# ProDoc_Board_ESP_AI_2024-12-05.net
KiCad netlist of a schematic drawn in EasyEDA Pro
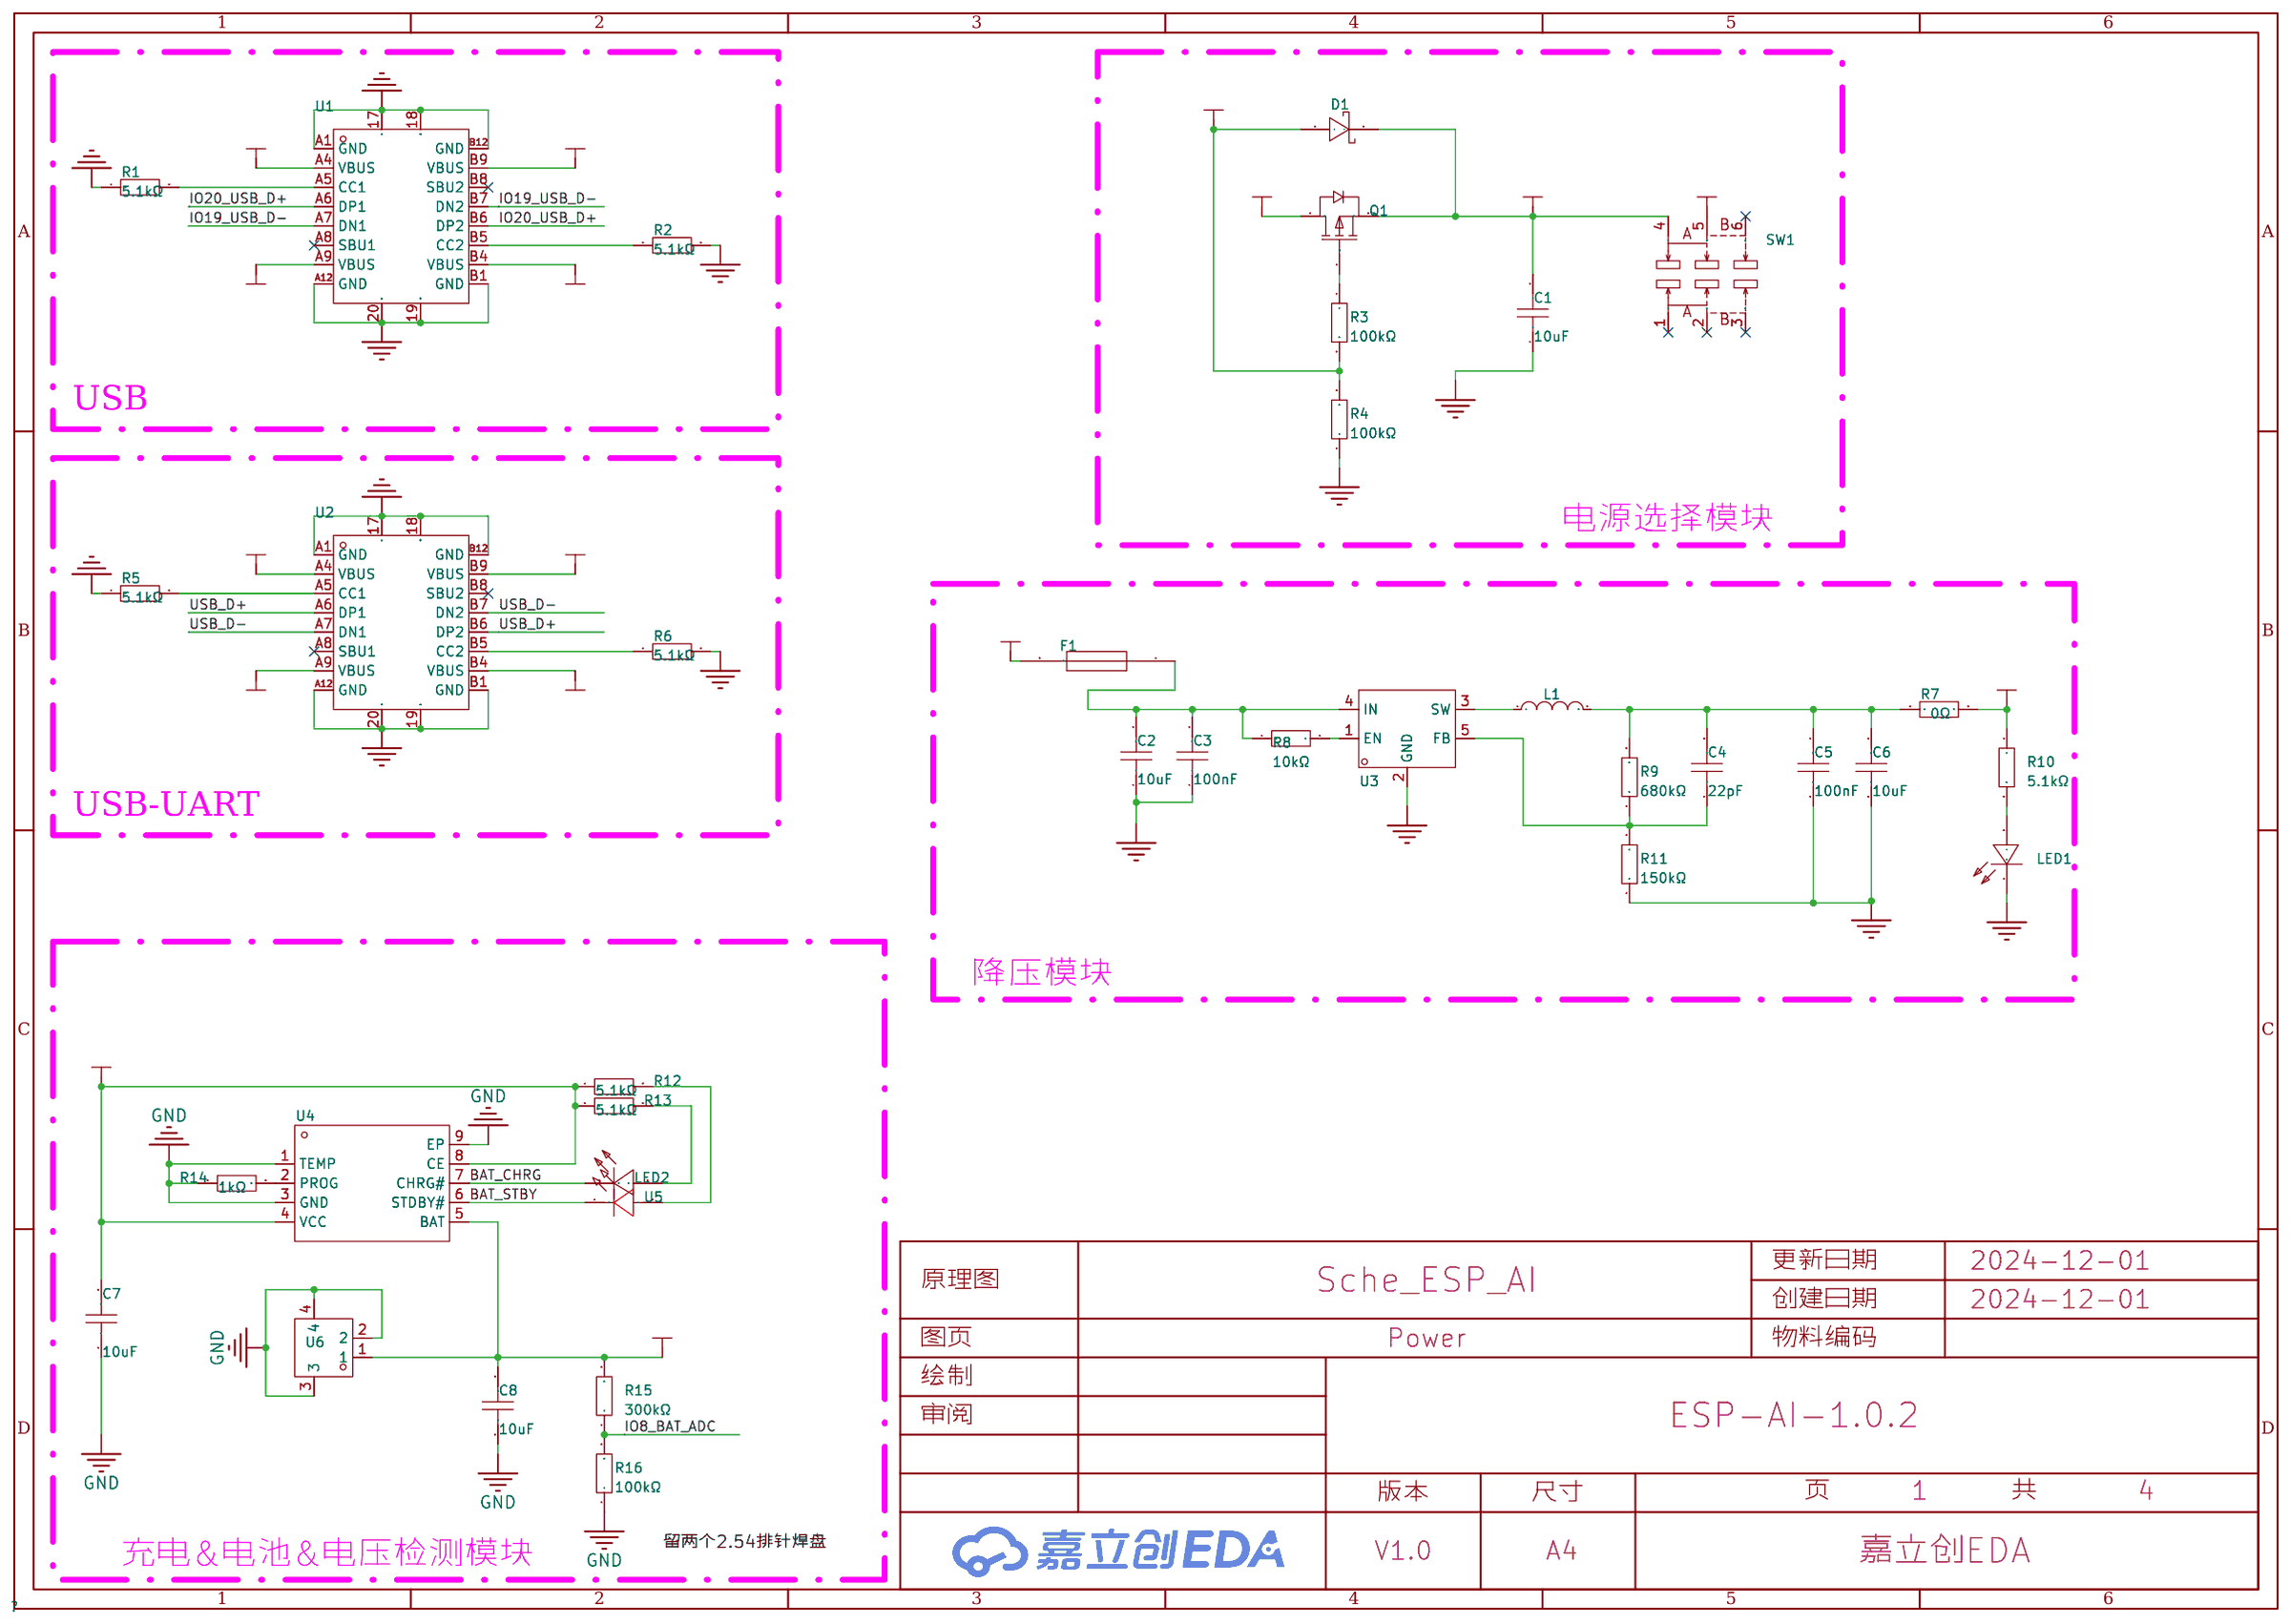
[diagram p0: Power]
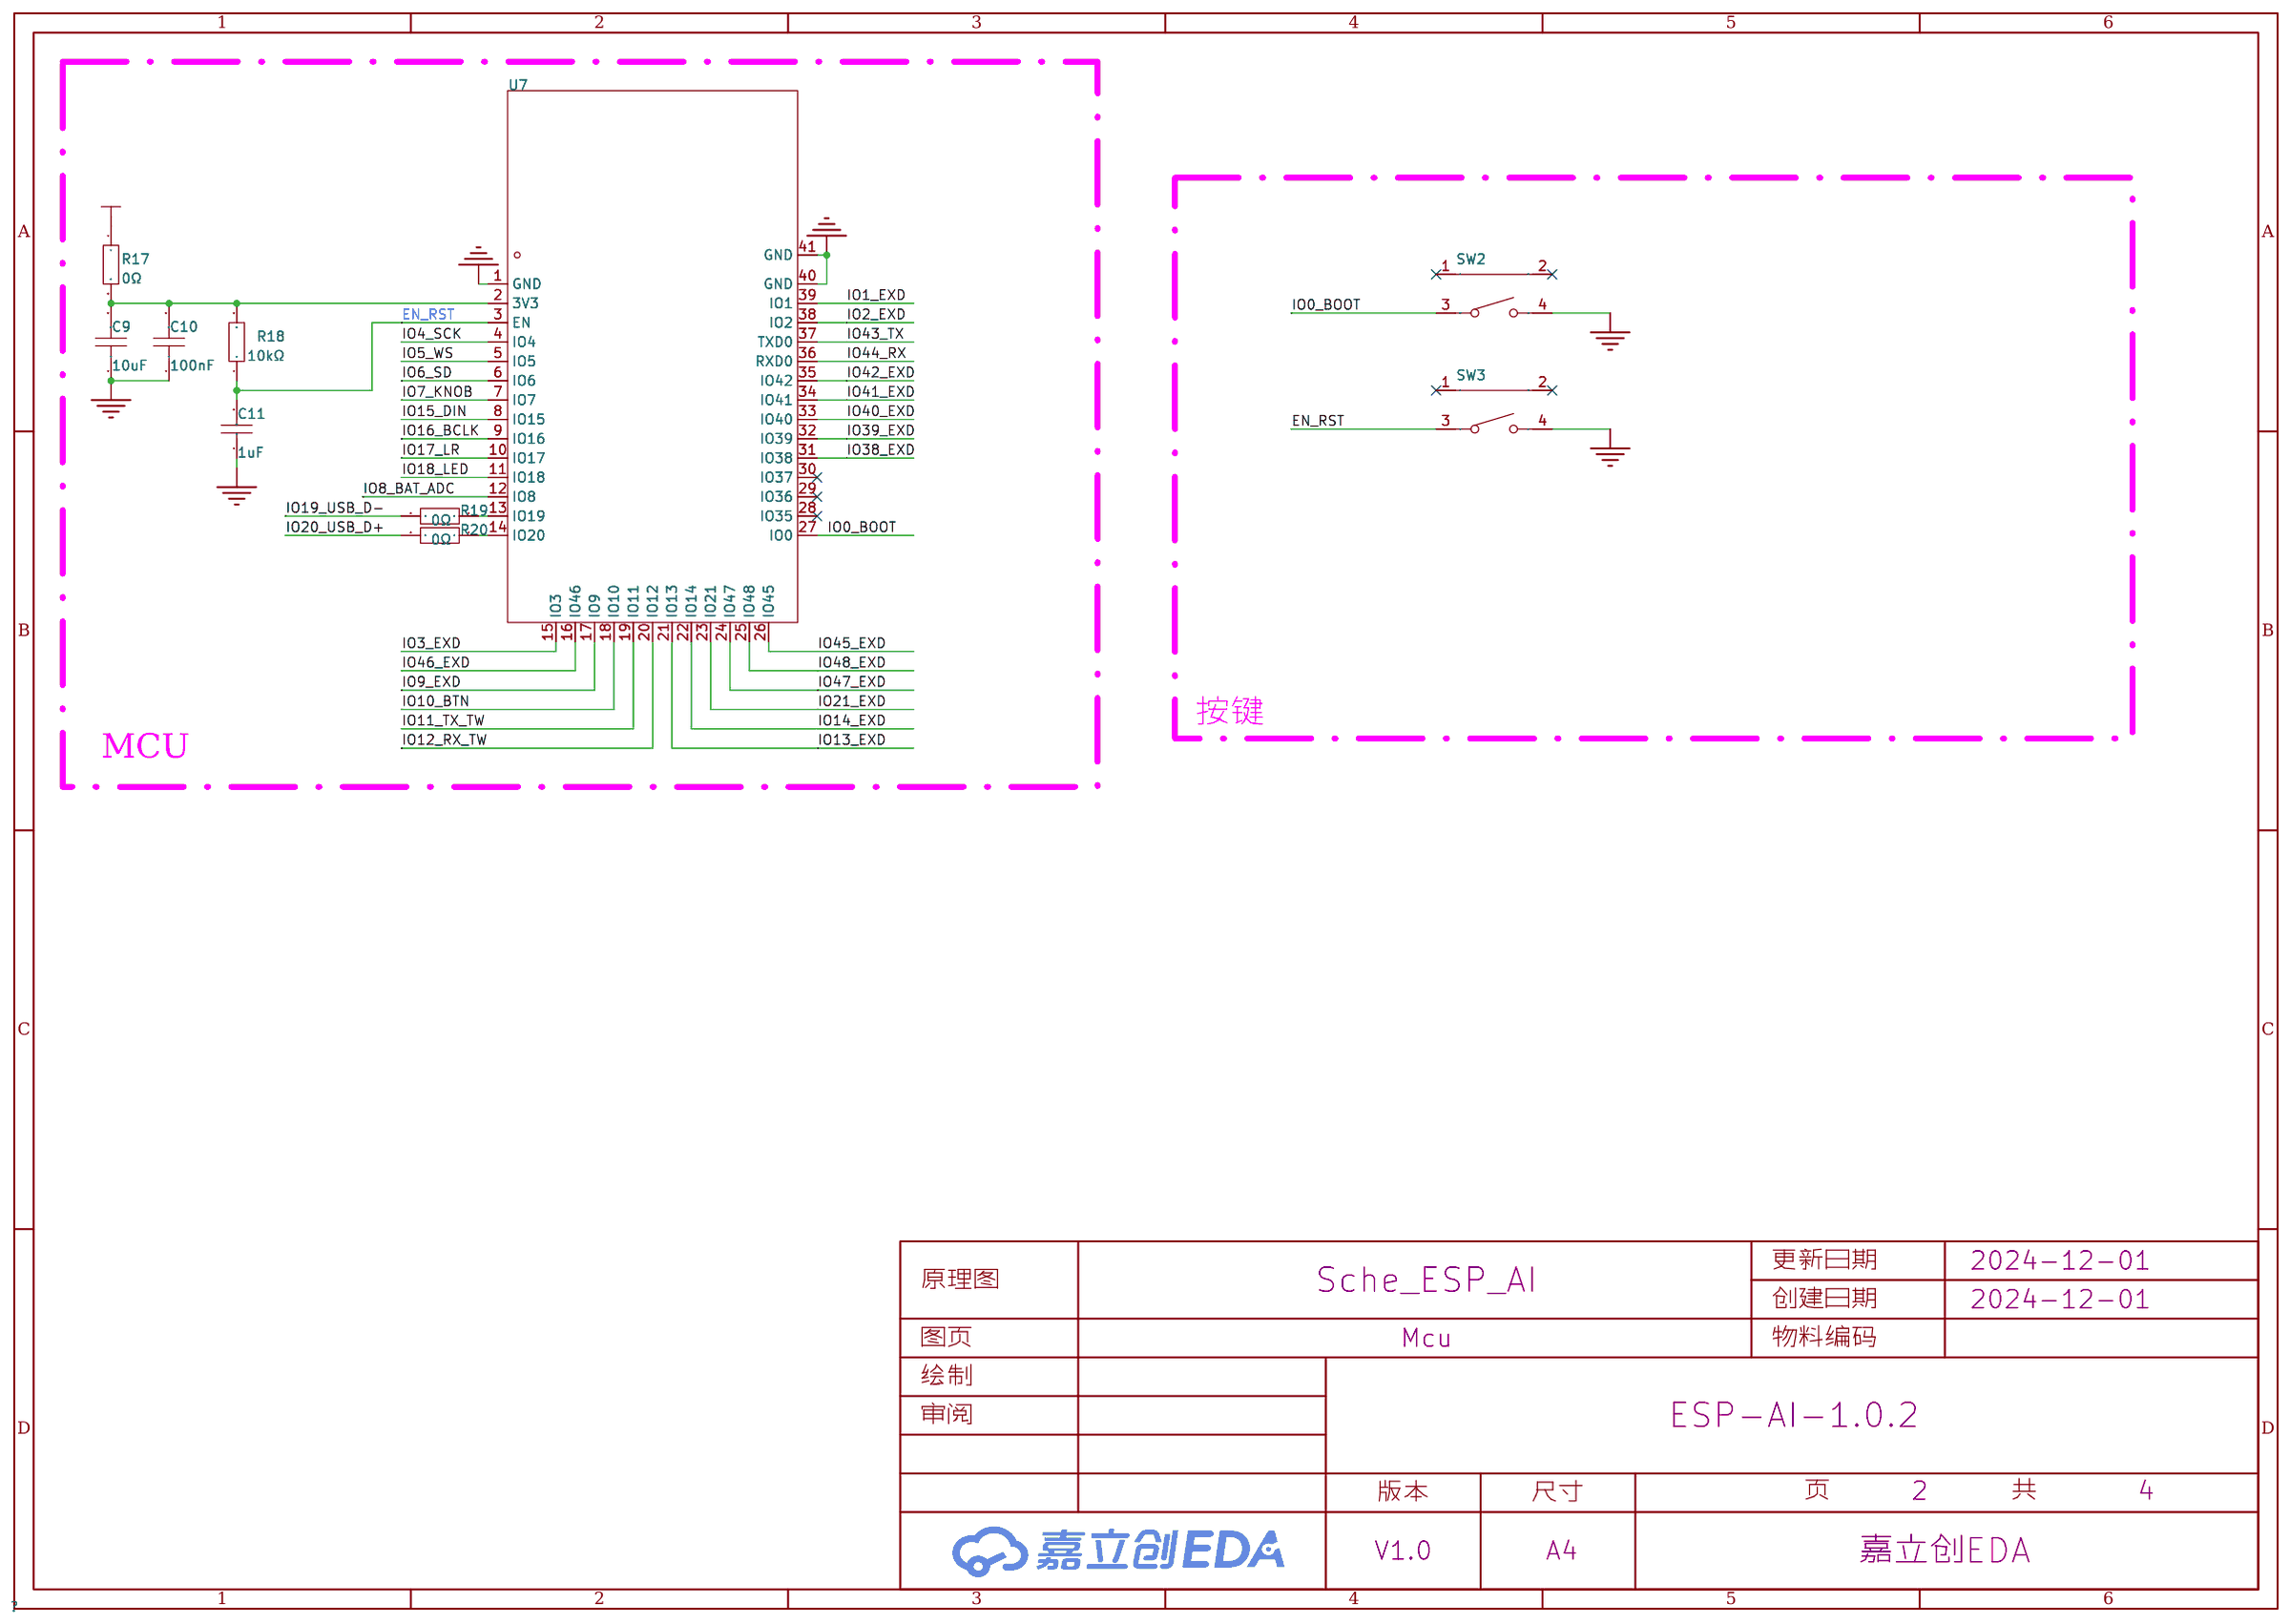
[diagram p1: Mcu]
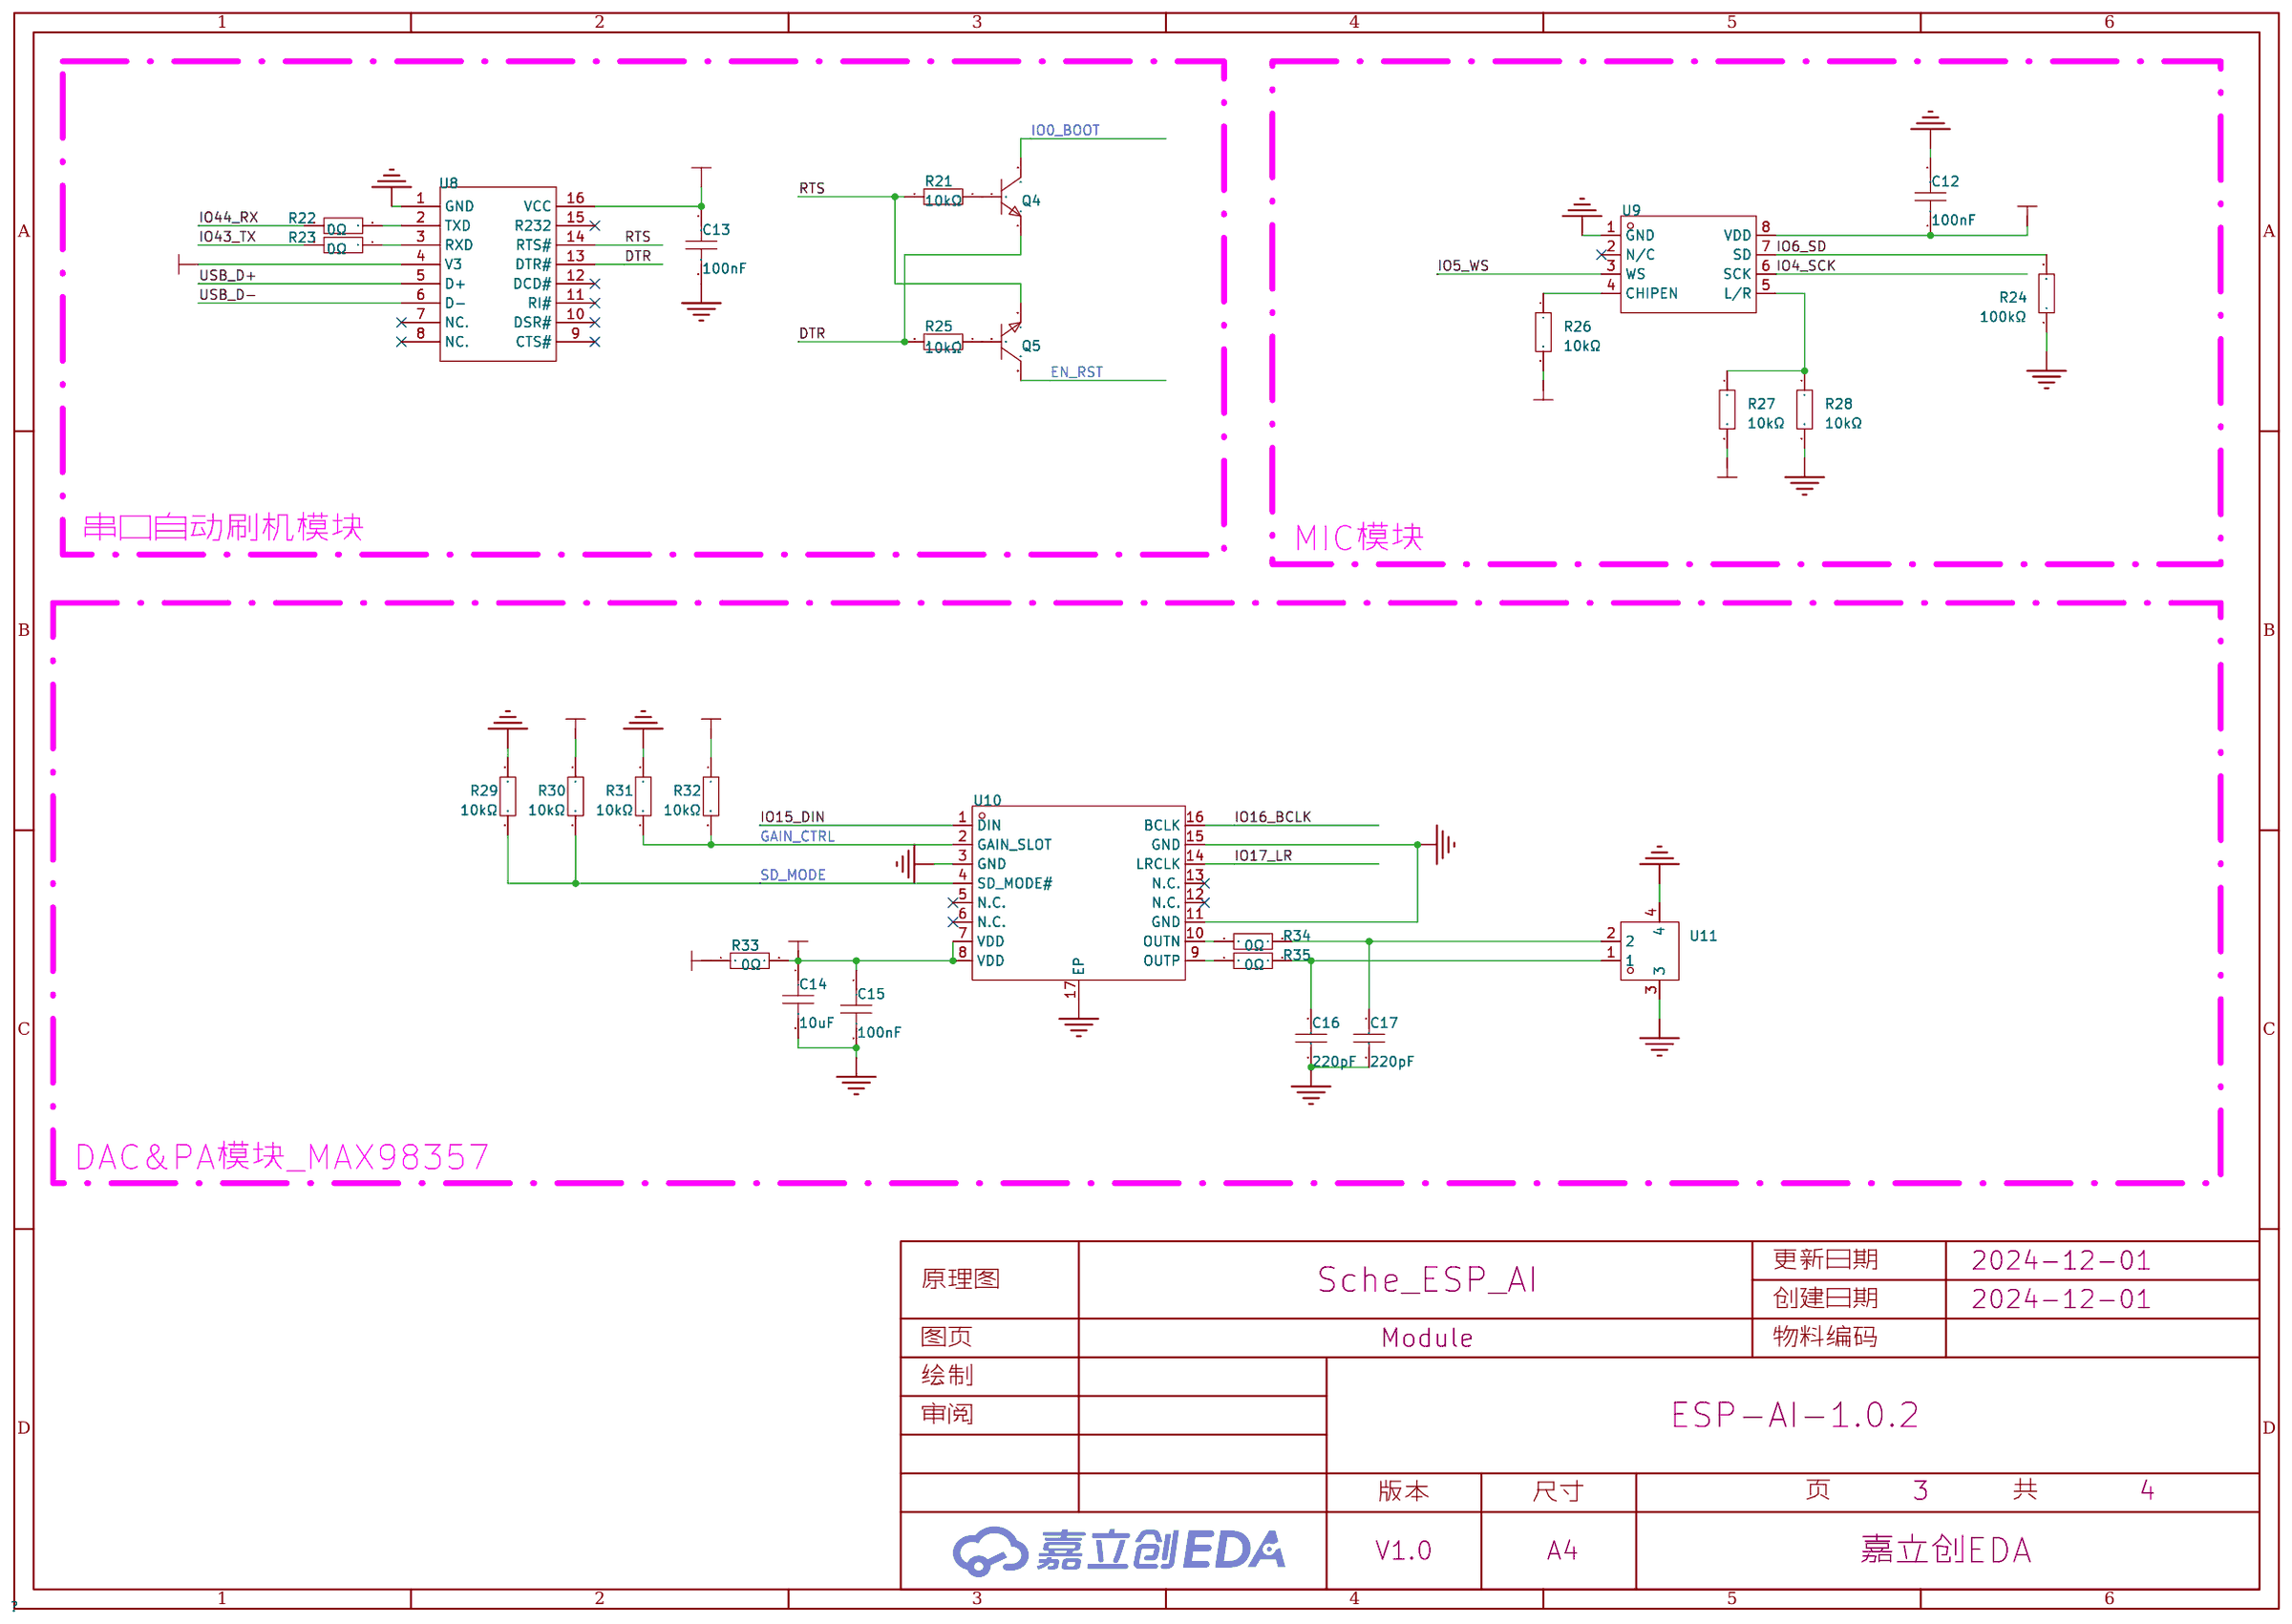
[diagram p2: Module]
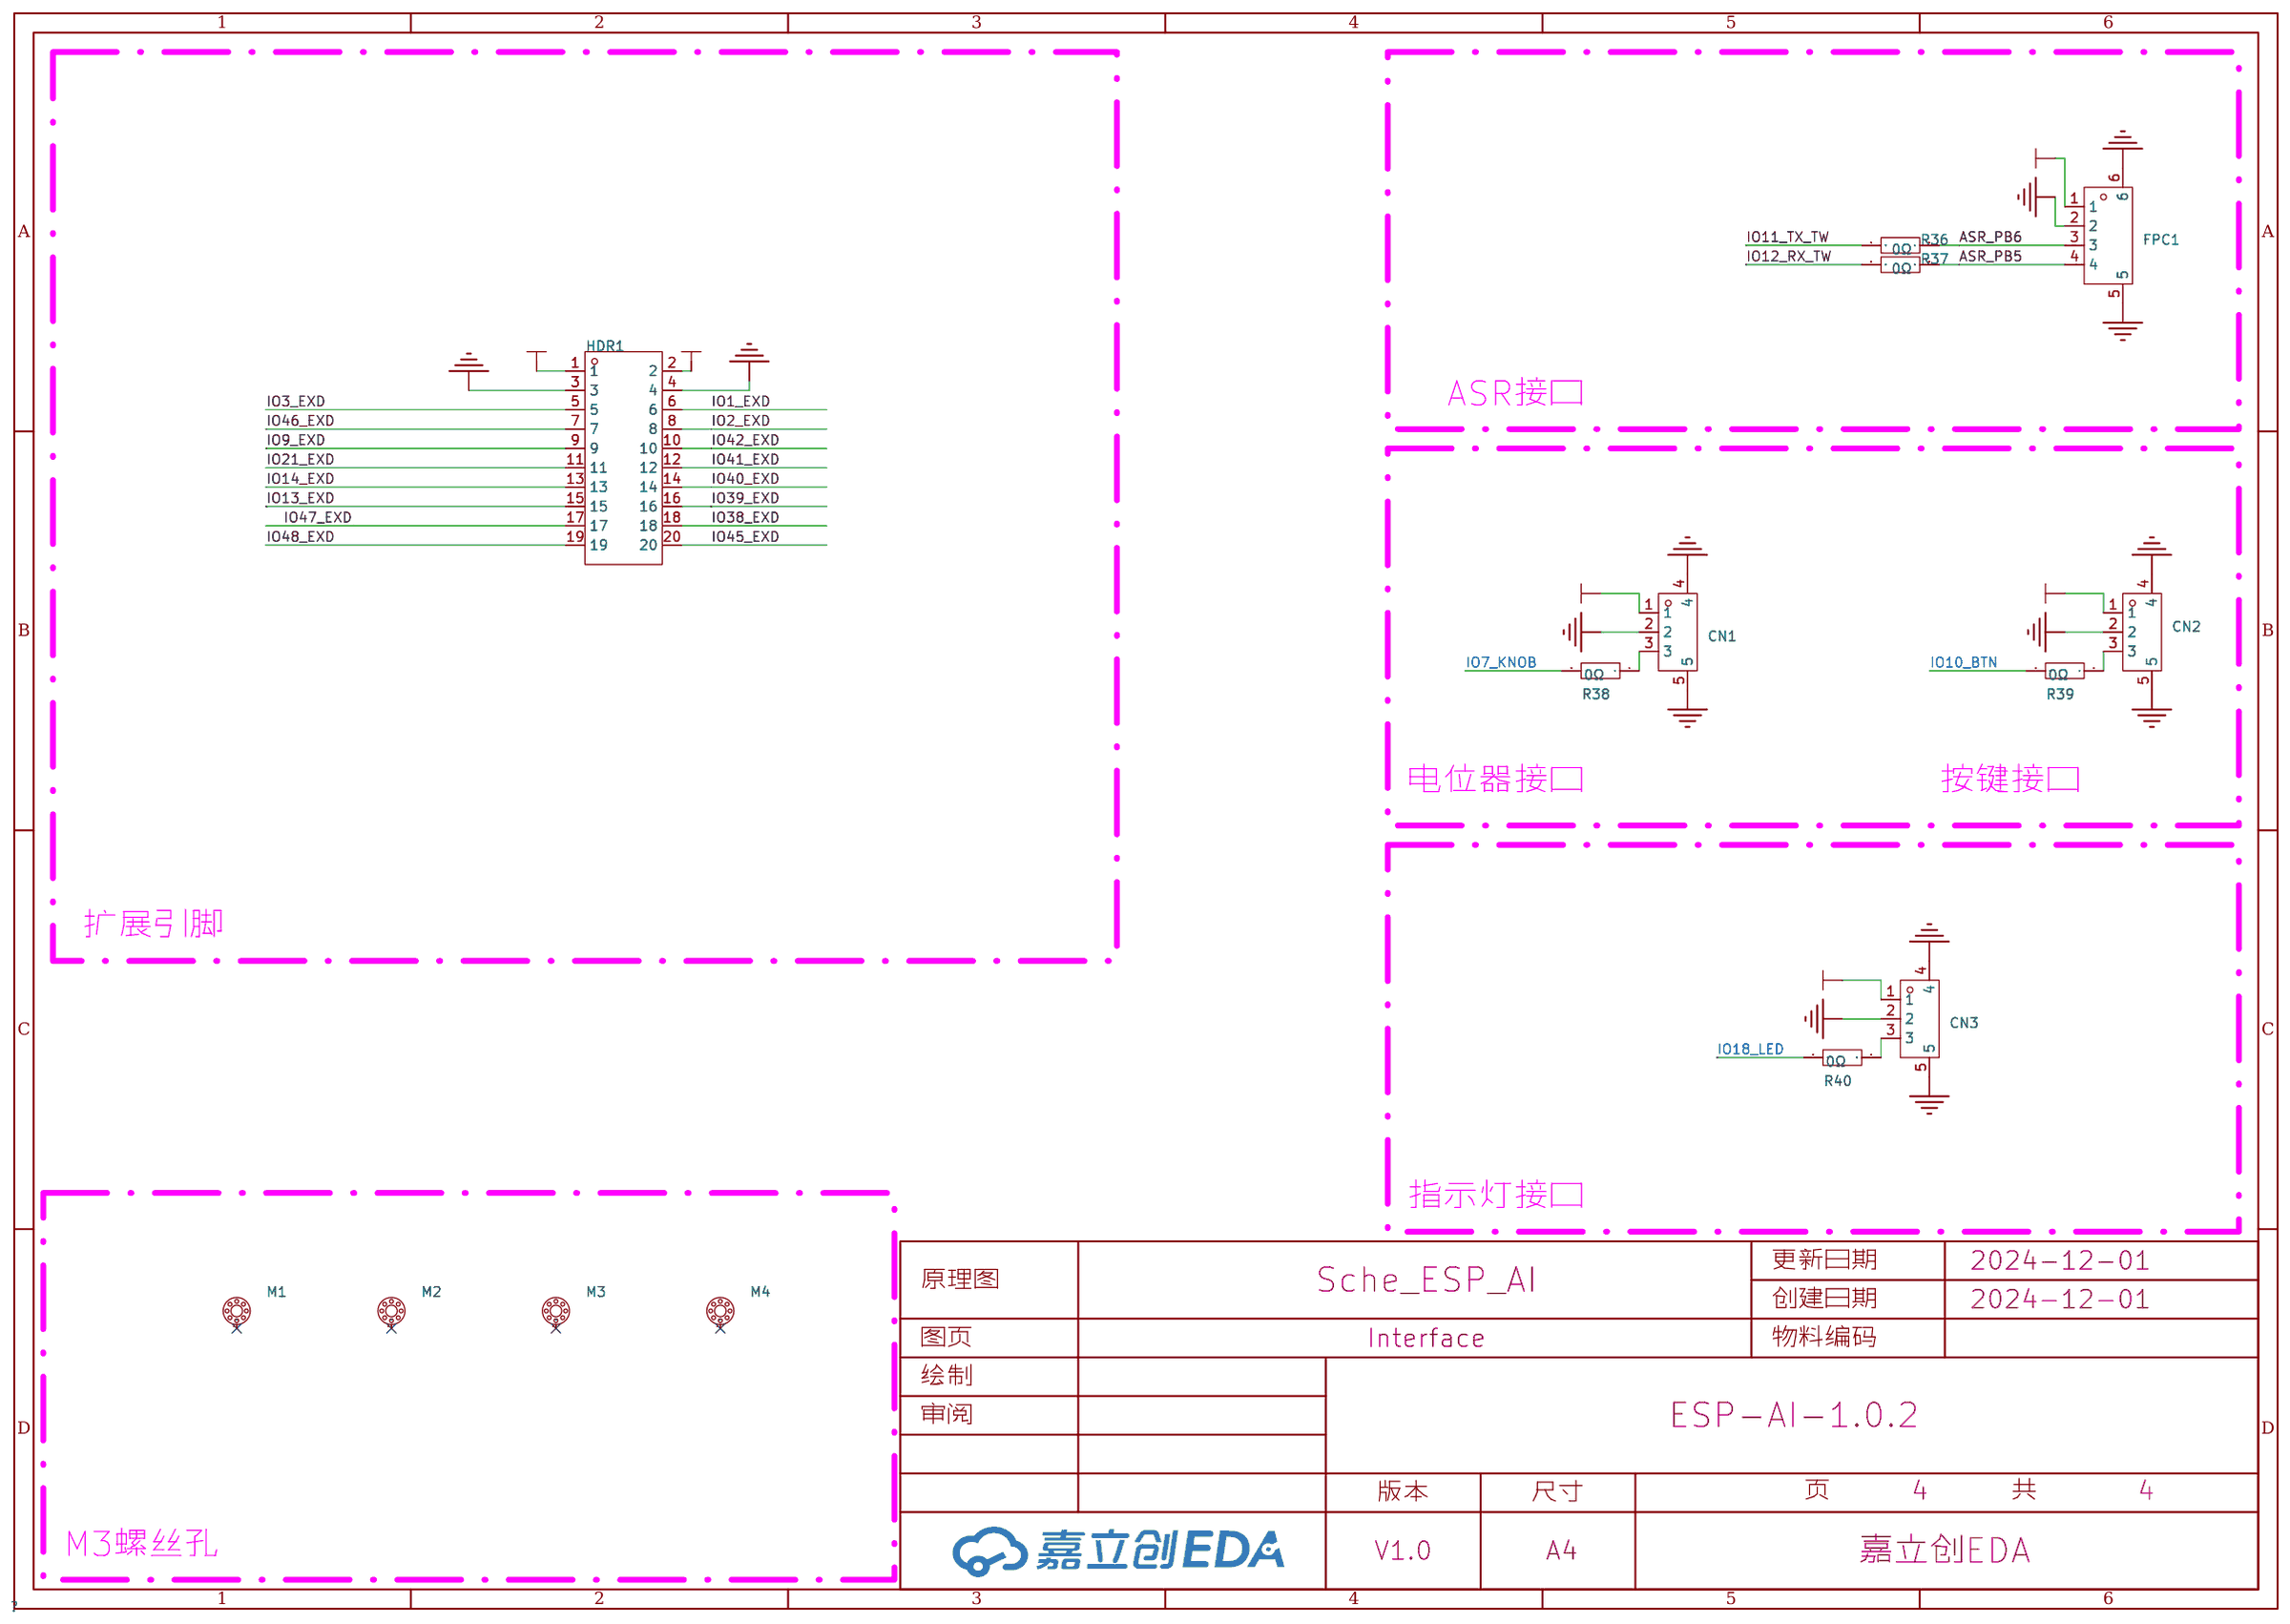
[diagram p3: Interface]

(export (version "E")
  (design (tool "Eeschema 10.0.6"))
  (components
    (comp (ref "C1")
      (value "10uF")
      (footprint "easyedapro:C0603")
      (description "容值:10uF;精度:±10%;额定电压:10V;材质(温度系数):X5R;")
      (fields
        (field (name "Manufacturer Part") "CL10A106KP8NNNC")
        (field (name "Manufacturer") "SAMSUNG(三星)")
      )
      (libsource (lib "easyedapro") (part "CL10A106KP8NNNC"))
    )
    (comp (ref "C2")
      (value "10uF")
      (footprint "easyedapro:C0603")
      (description "容值:10uF;精度:±10%;额定电压:10V;材质(温度系数):X5R;")
      (fields
        (field (name "Manufacturer Part") "CL10A106KP8NNNC")
        (field (name "Manufacturer") "SAMSUNG(三星)")
      )
      (libsource (lib "easyedapro") (part "CL10A106KP8NNNC"))
    )
    (comp (ref "C3")
      (value "100nF")
      (footprint "easyedapro:C0603")
      (description "容值:100nF;精度:±10%;额定电压:50V;材质(温度系数):X7R;")
      (fields
        (field (name "Manufacturer Part") "CC0603KRX7R9BB104")
        (field (name "Manufacturer") "YAGEO(国巨)")
      )
      (libsource (lib "easyedapro") (part "CC0603KRX7R9BB104"))
    )
    (comp (ref "C4")
      (value "22pF")
      (footprint "easyedapro:C0603")
      (description "容值:100nF;精度:±10%;额定电压:50V;材质(温度系数):X7R;")
      (fields
        (field (name "Manufacturer Part") "CL10C220JB8NNNC")
        (field (name "Manufacturer") "SAMSUNG(三星)")
      )
      (libsource (lib "easyedapro") (part "CC0603KRX7R9BB104"))
    )
    (comp (ref "C5")
      (value "100nF")
      (footprint "easyedapro:C0603")
      (description "容值:100nF;精度:±10%;额定电压:50V;材质(温度系数):X7R;")
      (fields
        (field (name "Manufacturer Part") "CC0603KRX7R9BB104")
        (field (name "Manufacturer") "YAGEO(国巨)")
      )
      (libsource (lib "easyedapro") (part "CC0603KRX7R9BB104"))
    )
    (comp (ref "C6")
      (value "10uF")
      (footprint "easyedapro:C0603")
      (description "容值:10uF;精度:±10%;额定电压:10V;材质(温度系数):X5R;")
      (fields
        (field (name "Manufacturer Part") "CL10A106KP8NNNC")
        (field (name "Manufacturer") "SAMSUNG(三星)")
      )
      (libsource (lib "easyedapro") (part "CL10A106KP8NNNC"))
    )
    (comp (ref "C7")
      (value "10uF")
      (footprint "easyedapro:C0603")
      (description "容值:10uF;精度:±10%;额定电压:10V;材质(温度系数):X5R;")
      (fields
        (field (name "Manufacturer Part") "CL10A106KP8NNNC")
        (field (name "Manufacturer") "SAMSUNG(三星)")
      )
      (libsource (lib "easyedapro") (part "CL10A106KP8NNNC"))
    )
    (comp (ref "C8")
      (value "10uF")
      (footprint "easyedapro:C0603")
      (description "容值:10uF;精度:±10%;额定电压:10V;材质(温度系数):X5R;")
      (fields
        (field (name "Manufacturer Part") "CL10A106KP8NNNC")
        (field (name "Manufacturer") "SAMSUNG(三星)")
      )
      (libsource (lib "easyedapro") (part "CL10A106KP8NNNC"))
    )
    (comp (ref "D1")
      (value "B5819W SL")
      (footprint "easyedapro:SOD-123_L2.7-W1.6-LS3.7-RD-1")
      (description "正向压降(Vf):600mV@1A;直流反向耐压(Vr):40V;整流电流:1A;")
      (fields (field (name "Manufacturer") "CJ(江苏长电/长晶)"))
      (libsource (lib "easyedapro") (part "B5819W_C8598"))
    )
    (comp (ref "F1")
      (value "JK-SMD0603-100L")
      (footprint "easyedapro:F0603")
      (description "最大电压:6V;最大电流:50A;保持电流:1A;跳闸电流:2A;")
      (fields (field (name "Manufacturer") "JK(金科)"))
      (libsource (lib "easyedapro") (part "JK-SMD0603-100L"))
    )
    (comp (ref "L1")
      (value "2.2uH")
      (footprint "easyedapro:IND-SMD_L4.0-W4.0")
      (description "电感值:2.2uH;精度:±20%;额定电流:2.2A;饱和电流(Isat):3A;类型:-;")
      (fields (field (name "Manufacturer Part") "SPH4018H2R2MT") (field (name "Manufacturer") "Sunlord(顺络)"))
      (libsource (lib "easyedapro") (part "SPH4018H2R2MT"))
    )
    (comp (ref "LED1")
      (value "KT-0603R")
      (footprint "easyedapro:LED0603-RD")
      (description "发光颜色:红色;功率:-;正向电流:-;主波长:-;二极管配置:-;透镜颜色:-;色温:-;发光角度:-;载带方式:-;工作温度:-40°C~+85°C;")
      (fields (field (name "Manufacturer") "KENTO"))
      (libsource (lib "easyedapro") (part "KT-0603R"))
    )
    (comp (ref "LED2")
      (value "KT-0603R")
      (footprint "easyedapro:LED0603-RD")
      (description "发光颜色:红色;功率:-;正向电流:-;主波长:-;二极管配置:-;透镜颜色:-;色温:-;发光角度:-;载带方式:-;工作温度:-40°C~+85°C;")
      (fields (field (name "Manufacturer") "KENTO"))
      (libsource (lib "easyedapro") (part "KT-0603R"))
    )
    (comp (ref "Q1")
      (value "AO3401A")
      (footprint "easyedapro:SOT-23_L2.9-W1.3-P1.90-LS2.4-BR")
      (fields (field (name "Manufacturer") "AOS"))
      (libsource (lib "easyedapro") (part "AO3401A"))
    )
    (comp (ref "R1")
      (value "5.1kΩ")
      (footprint "easyedapro:R0603")
      (description "电阻类型:厚膜电阻;阻值:5.1kΩ;精度:±1%;功率:100mW;最大工作电压:75V;温度系数:±100ppm/°C;")
      (fields
        (field (name "Manufacturer Part") "0603WAF5101T5E")
        (field (name "Manufacturer") "UNI-ROYAL(厚声)")
      )
      (libsource (lib "easyedapro") (part "0603WAF5101T5E"))
    )
    (comp (ref "R2")
      (value "5.1kΩ")
      (footprint "easyedapro:R0603")
      (description "电阻类型:厚膜电阻;阻值:5.1kΩ;精度:±1%;功率:100mW;最大工作电压:75V;温度系数:±100ppm/°C;")
      (fields
        (field (name "Manufacturer Part") "0603WAF5101T5E")
        (field (name "Manufacturer") "UNI-ROYAL(厚声)")
      )
      (libsource (lib "easyedapro") (part "0603WAF5101T5E"))
    )
    (comp (ref "R3")
      (value "100kΩ")
      (footprint "easyedapro:R0603")
      (description "电阻类型:厚膜电阻;阻值:100kΩ;精度:±1%;功率:100mW;最大工作电压:75V;温度系数:±100ppm/°C;")
      (fields
        (field (name "Manufacturer Part") "0603WAF1003T5E")
        (field (name "Manufacturer") "UNI-ROYAL(厚声)")
      )
      (libsource (lib "easyedapro") (part "0603WAF1003T5E"))
    )
    (comp (ref "R4")
      (value "100kΩ")
      (footprint "easyedapro:R0603")
      (description "电阻类型:厚膜电阻;阻值:100kΩ;精度:±1%;功率:100mW;最大工作电压:75V;温度系数:±100ppm/°C;")
      (fields
        (field (name "Manufacturer Part") "0603WAF1003T5E")
        (field (name "Manufacturer") "UNI-ROYAL(厚声)")
      )
      (libsource (lib "easyedapro") (part "0603WAF1003T5E"))
    )
    (comp (ref "R5")
      (value "5.1kΩ")
      (footprint "easyedapro:R0603")
      (description "电阻类型:厚膜电阻;阻值:5.1kΩ;精度:±1%;功率:100mW;最大工作电压:75V;温度系数:±100ppm/°C;")
      (fields
        (field (name "Manufacturer Part") "0603WAF5101T5E")
        (field (name "Manufacturer") "UNI-ROYAL(厚声)")
      )
      (libsource (lib "easyedapro") (part "0603WAF5101T5E"))
    )
    (comp (ref "R6")
      (value "5.1kΩ")
      (footprint "easyedapro:R0603")
      (description "电阻类型:厚膜电阻;阻值:5.1kΩ;精度:±1%;功率:100mW;最大工作电压:75V;温度系数:±100ppm/°C;")
      (fields
        (field (name "Manufacturer Part") "0603WAF5101T5E")
        (field (name "Manufacturer") "UNI-ROYAL(厚声)")
      )
      (libsource (lib "easyedapro") (part "0603WAF5101T5E"))
    )
    (comp (ref "R7")
      (value "0Ω")
      (footprint "easyedapro:R0603_1")
      (description "电阻类型:厚膜电阻;阻值:0Ω;精度:±1%;功率:100mW;最大工作电压:75V;")
      (fields
        (field (name "Manufacturer Part") "0603WAF0000T5E")
        (field (name "Manufacturer") "UNI-ROYAL(厚声)")
      )
      (libsource (lib "easyedapro") (part "0603WAF0000T5E"))
    )
    (comp (ref "R8")
      (value "10kΩ")
      (footprint "easyedapro:R0603_1")
      (description "电阻类型:厚膜电阻;阻值:10kΩ;精度:±1%;功率:100mW;最大工作电压:75V;温度系数:±100ppm/℃;")
      (fields
        (field (name "Manufacturer Part") "0603WAF1002T5E")
        (field (name "Manufacturer") "UNI-ROYAL(厚声)")
      )
      (libsource (lib "easyedapro") (part "0603WAF1002T5E"))
    )
    (comp (ref "R9")
      (value "680kΩ")
      (footprint "easyedapro:R0603_1")
      (description "电阻类型:厚膜电阻;阻值:680kΩ;精度:±1%;功率:100mW;最大工作电压:75V;温度系数:±100ppm/℃;")
      (fields
        (field (name "Manufacturer Part") "0603WAF6803T5E")
        (field (name "Manufacturer") "UNI-ROYAL(厚声)")
      )
      (libsource (lib "easyedapro") (part "0603WAF6803T5E"))
    )
    (comp (ref "R10")
      (value "5.1kΩ")
      (footprint "easyedapro:R0603")
      (description "电阻类型:厚膜电阻;阻值:5.1kΩ;精度:±1%;功率:100mW;最大工作电压:75V;温度系数:±100ppm/°C;")
      (fields
        (field (name "Manufacturer Part") "0603WAF5101T5E")
        (field (name "Manufacturer") "UNI-ROYAL(厚声)")
      )
      (libsource (lib "easyedapro") (part "0603WAF5101T5E"))
    )
    (comp (ref "R11")
      (value "150kΩ")
      (footprint "easyedapro:R0603_1")
      (description "电阻类型:厚膜电阻;阻值:150kΩ;精度:±1%;功率:100mW;最大工作电压:75V;温度系数:±100ppm/℃;")
      (fields
        (field (name "Manufacturer Part") "0603WAF1503T5E")
        (field (name "Manufacturer") "UNI-ROYAL(厚声)")
      )
      (libsource (lib "easyedapro") (part "0603WAF1503T5E"))
    )
    (comp (ref "R12")
      (value "5.1kΩ")
      (footprint "easyedapro:R0603")
      (description "电阻类型:厚膜电阻;阻值:5.1kΩ;精度:±1%;功率:100mW;最大工作电压:75V;温度系数:±100ppm/°C;")
      (fields
        (field (name "Manufacturer Part") "0603WAF5101T5E")
        (field (name "Manufacturer") "UNI-ROYAL(厚声)")
      )
      (libsource (lib "easyedapro") (part "0603WAF5101T5E"))
    )
    (comp (ref "R13")
      (value "5.1kΩ")
      (footprint "easyedapro:R0603")
      (description "电阻类型:厚膜电阻;阻值:5.1kΩ;精度:±1%;功率:100mW;最大工作电压:75V;温度系数:±100ppm/°C;")
      (fields
        (field (name "Manufacturer Part") "0603WAF5101T5E")
        (field (name "Manufacturer") "UNI-ROYAL(厚声)")
      )
      (libsource (lib "easyedapro") (part "0603WAF5101T5E"))
    )
    (comp (ref "R14")
      (value "1kΩ")
      (footprint "easyedapro:R0603")
      (description "电阻类型:厚膜电阻;阻值:1kΩ;精度:±1%;功率:100mW;最大工作电压:75V;温度系数:±100ppm/°C;")
      (fields
        (field (name "Manufacturer Part") "0603WAF1001T5E")
        (field (name "Manufacturer") "UNI-ROYAL(厚声)")
      )
      (libsource (lib "easyedapro") (part "0603WAF1001T5E"))
    )
    (comp (ref "R15")
      (value "300kΩ")
      (footprint "easyedapro:R0603")
      (description "电阻类型:厚膜电阻;阻值:300kΩ;精度:±1%;功率:100mW;最大工作电压:75V;温度系数:±100ppm/°C;")
      (fields
        (field (name "Manufacturer Part") "0603WAF3003T5E")
        (field (name "Manufacturer") "UNI-ROYAL(厚声)")
      )
      (libsource (lib "easyedapro") (part "0603WAF3003T5E"))
    )
    (comp (ref "R16")
      (value "100kΩ")
      (footprint "easyedapro:R0603")
      (description "电阻类型:厚膜电阻;阻值:100kΩ;精度:±1%;功率:100mW;最大工作电压:75V;温度系数:±100ppm/°C;")
      (fields
        (field (name "Manufacturer Part") "0603WAF1003T5E")
        (field (name "Manufacturer") "UNI-ROYAL(厚声)")
      )
      (libsource (lib "easyedapro") (part "0603WAF1003T5E"))
    )
    (comp (ref "SW1")
      (value "MST22D18G2 125")
      (footprint "easyedapro:SW-SMD_MST22D18G2")
      (description "电路结构:双刀双掷;安装方式:立贴;开关颜色:黑色;额定电流(DC):100mA;额定电压(DC):12V;机械寿命:1万次;")
      (fields (field (name "Manufacturer") "SHOU HAN(首韩)"))
      (libsource (lib "easyedapro") (part "MST22D18G2 125"))
    )
    (comp (ref "U1")
      (value "24018-UCAF001-A")
      (footprint "easyedapro:TYPE-C-USB-SMD_CF003")
      (description "TYPE C 16P母座加高1.0 H=4.25无弹")
      (fields (field (name "Manufacturer") "MINTRON(明硕)"))
      (libsource (lib "easyedapro") (part "24018-UCAF001-A"))
    )
    (comp (ref "U2")
      (value "24018-UCAF001-A")
      (footprint "easyedapro:TYPE-C-USB-SMD_CF003")
      (description "TYPE C 16P母座加高1.0 H=4.25无弹")
      (fields (field (name "Manufacturer") "MINTRON(明硕)"))
      (libsource (lib "easyedapro") (part "24018-UCAF001-A"))
    )
    (comp (ref "U3")
      (value "ETA3409S2F")
      (footprint "easyedapro:SOT-23-5_L2.9-W1.6-P0.95-LS2.8-BL_1")
      (fields (field (name "Manufacturer") "ETA(钰泰）"))
      (libsource (lib "easyedapro") (part "ETA3409S2F"))
    )
    (comp (ref "U4")
      (value "AP5056")
      (footprint "easyedapro:SOP-8_L4.9-W3.9-P1.27-LS6.0-BL-EP")
      (description "常用锂电池充电芯片，功能同TP4056")
      (fields (field (name "Manufacturer") "chipown(芯朋微电子)"))
      (libsource (lib "easyedapro") (part "AP5056"))
    )
    (comp (ref "U5")
      (value "19-217/GHC-YR1S2/6T")
      (footprint "easyedapro:LED0603-RD_GREEN")
      (fields (field (name "Manufacturer") "EVERLIGHT(亿光)"))
      (libsource (lib "easyedapro") (part "19-217/ghc-yr1s2/6t"))
    )
    (comp (ref "U6")
      (value "HCZZ0015-2")
      (footprint "easyedapro:CONN-SMD_HCZZ0015-2")
      (fields (field (name "Manufacturer") "HC(虹成电子)"))
      (libsource (lib "easyedapro") (part "HCZZ0015-2"))
    )
    (comp (ref "C9")
      (value "10uF")
      (footprint "easyedapro:C0603")
      (description "容值:10uF;精度:±10%;额定电压:10V;材质(温度系数):X5R;")
      (fields
        (field (name "Manufacturer Part") "CL10A106KP8NNNC")
        (field (name "Manufacturer") "SAMSUNG(三星)")
      )
      (libsource (lib "easyedapro") (part "CL10A106KP8NNNC"))
    )
    (comp (ref "C10")
      (value "100nF")
      (footprint "easyedapro:C0603")
      (description "容值:100nF;精度:±10%;额定电压:50V;材质(温度系数):X7R;")
      (fields
        (field (name "Manufacturer Part") "CC0603KRX7R9BB104")
        (field (name "Manufacturer") "YAGEO(国巨)")
      )
      (libsource (lib "easyedapro") (part "CC0603KRX7R9BB104"))
    )
    (comp (ref "C11")
      (value "1uF")
      (footprint "easyedapro:C0603_1")
      (description "容值:1uF;精度:±10%;额定电压:50V;材质(温度系数):X5R;")
      (fields
        (field (name "Manufacturer Part") "CL10A105KB8NNNC")
        (field (name "Manufacturer") "SAMSUNG(三星)")
      )
      (libsource (lib "easyedapro") (part "CL10A105KB8NNNC"))
    )
    (comp (ref "R17")
      (value "0Ω")
      (footprint "easyedapro:R0603_1")
      (description "电阻类型:厚膜电阻;阻值:0Ω;精度:±1%;功率:100mW;")
      (fields
        (field (name "Manufacturer Part") "0603WAF0000T5E")
        (field (name "Manufacturer") "UNI-ROYAL(厚声)")
      )
      (libsource (lib "easyedapro") (part "0603WAF0000T5E"))
    )
    (comp (ref "R18")
      (value "10kΩ")
      (footprint "easyedapro:R0603_1")
      (description "电阻类型:厚膜电阻;阻值:10kΩ;精度:±1%;功率:100mW;")
      (fields
        (field (name "Manufacturer Part") "0603WAF1002T5E")
        (field (name "Manufacturer") "UNI-ROYAL(厚声)")
      )
      (libsource (lib "easyedapro") (part "0603WAF1002T5E"))
    )
    (comp (ref "R19")
      (value "0Ω")
      (footprint "easyedapro:R0603_1")
      (description "电阻类型:厚膜电阻;阻值:0Ω;精度:±1%;功率:100mW;")
      (fields
        (field (name "Manufacturer Part") "0603WAF0000T5E")
        (field (name "Manufacturer") "UNI-ROYAL(厚声)")
      )
      (libsource (lib "easyedapro") (part "0603WAF0000T5E"))
    )
    (comp (ref "R20")
      (value "0Ω")
      (footprint "easyedapro:R0603_1")
      (description "电阻类型:厚膜电阻;阻值:0Ω;精度:±1%;功率:100mW;")
      (fields
        (field (name "Manufacturer Part") "0603WAF0000T5E")
        (field (name "Manufacturer") "UNI-ROYAL(厚声)")
      )
      (libsource (lib "easyedapro") (part "0603WAF0000T5E"))
    )
    (comp (ref "SW2")
      (value "TS24CA")
      (footprint "easyedapro:SW-SMD_TS24CA")
      (description "电路结构:单刀单掷;按钮形状:矩形按钮;安装方式:卧贴;开关长度:4.55mm;开关宽度:1.8mm;开关高度:3.5mm;触点电流:50mA;额定电压(DC):12V;带灯:-;机械寿命:-;")
      (fields (field (name "Manufacturer") "SHOU HAN(首韩)"))
      (libsource (lib "easyedapro") (part "TS24CA"))
    )
    (comp (ref "SW3")
      (value "TS24CA")
      (footprint "easyedapro:SW-SMD_TS24CA")
      (description "电路结构:单刀单掷;按钮形状:矩形按钮;安装方式:卧贴;开关长度:4.55mm;开关宽度:1.8mm;开关高度:3.5mm;触点电流:50mA;额定电压(DC):12V;带灯:-;机械寿命:-;")
      (fields (field (name "Manufacturer") "SHOU HAN(首韩)"))
      (libsource (lib "easyedapro") (part "TS24CA"))
    )
    (comp (ref "U7")
      (value "ESP32-S3-WROOM-1-N16R8")
      (footprint "easyedapro:WIRELM-SMD_ESP32-S3-WROOM-1")
      (fields (field (name "Manufacturer") "ESPRESSIF(乐鑫)"))
      (libsource (lib "easyedapro") (part "ESP32-S3-WROOM-1(N16R8)"))
    )
    (comp (ref "C12")
      (value "100nF")
      (footprint "easyedapro:C0603")
      (description "容值:100nF;精度:±10%;额定电压:50V;材质(温度系数):X7R;")
      (fields
        (field (name "Manufacturer Part") "CC0603KRX7R9BB104")
        (field (name "Manufacturer") "YAGEO(国巨)")
      )
      (libsource (lib "easyedapro") (part "CC0603KRX7R9BB104"))
    )
    (comp (ref "C13")
      (value "100nF")
      (fields
        (field (name "Manufacturer Part") "CC0603KRX7R9BB104")
        (field (name "Manufacturer") "YAGEO(国巨)")
      )
      (libsource (lib "easyedapro") (part "C1210X7R475K630NT"))
    )
    (comp (ref "C14")
      (value "10uF")
      (footprint "easyedapro:C0603")
      (description "容值:10uF;精度:±10%;额定电压:10V;材质(温度系数):X5R;")
      (fields
        (field (name "Manufacturer Part") "CL10A106KP8NNNC")
        (field (name "Manufacturer") "SAMSUNG(三星)")
      )
      (libsource (lib "easyedapro") (part "CL10A106KP8NNNC"))
    )
    (comp (ref "C15")
      (value "100nF")
      (footprint "easyedapro:C0603")
      (description "容值:100nF;精度:±10%;额定电压:50V;材质(温度系数):X7R;")
      (fields
        (field (name "Manufacturer Part") "CC0603KRX7R9BB104")
        (field (name "Manufacturer") "YAGEO(国巨)")
      )
      (libsource (lib "easyedapro") (part "CC0603KRX7R9BB104"))
    )
    (comp (ref "C16")
      (value "220pF")
      (footprint "easyedapro:C0603_1")
      (description "容值:220pF;精度:±10%;额定电压:50V;材质(温度系数):X7R;")
      (fields
        (field (name "Manufacturer Part") "CL10B221KB8NNNC")
        (field (name "Manufacturer") "SAMSUNG(三星)")
      )
      (libsource (lib "easyedapro") (part "CL10B221KB8NNNC"))
    )
    (comp (ref "C17")
      (value "220pF")
      (footprint "easyedapro:C0603_1")
      (description "容值:220pF;精度:±10%;额定电压:50V;材质(温度系数):X7R;")
      (fields
        (field (name "Manufacturer Part") "CL10B221KB8NNNC")
        (field (name "Manufacturer") "SAMSUNG(三星)")
      )
      (libsource (lib "easyedapro") (part "CL10B221KB8NNNC"))
    )
    (comp (ref "Q4")
      (value "SS8050")
      (footprint "easyedapro:SOT-23-3_L2.9-W1.3-P1.90-LS2.4-BR")
      (description "晶体管类型:NPN;集电极电流(Ic):1.5A;集射极击穿电压(Vceo):25V;功率(Pd):300mW;直流电流增益(hFE@Ic,Vce):200@100mA,1V;")
      (fields (field (name "Manufacturer") "CJ(江苏长电/长晶)"))
      (libsource (lib "easyedapro") (part "SS8050_C2150"))
    )
    (comp (ref "Q5")
      (value "SS8050")
      (footprint "easyedapro:SOT-23-3_L2.9-W1.3-P1.90-LS2.4-BR")
      (description "晶体管类型:NPN;集电极电流(Ic):1.5A;集射极击穿电压(Vceo):25V;功率(Pd):300mW;直流电流增益(hFE@Ic,Vce):200@100mA,1V;")
      (fields (field (name "Manufacturer") "CJ(江苏长电/长晶)"))
      (libsource (lib "easyedapro") (part "SS8050_C2150"))
    )
    (comp (ref "R21")
      (value "10kΩ")
      (description "电阻类型:厚膜电阻;阻值:10kΩ;精度:±1%;功率:100mW;最大工作电压:75V;温度系数:±100ppm/℃;")
      (fields
        (field (name "Manufacturer Part") "0603WAF1002T5E")
        (field (name "Manufacturer") "UNI-ROYAL(厚声)")
      )
      (libsource (lib "easyedapro") (part "电阻_1"))
    )
    (comp (ref "R22")
      (value "0Ω")
      (footprint "easyedapro:R0603_1")
      (description "电阻类型:厚膜电阻;阻值:0Ω;精度:±1%;功率:100mW;")
      (fields
        (field (name "Manufacturer Part") "0603WAF0000T5E")
        (field (name "Manufacturer") "UNI-ROYAL(厚声)")
      )
      (libsource (lib "easyedapro") (part "0603WAF0000T5E"))
    )
    (comp (ref "R23")
      (value "0Ω")
      (footprint "easyedapro:R0603_1")
      (description "电阻类型:厚膜电阻;阻值:0Ω;精度:±1%;功率:100mW;")
      (fields
        (field (name "Manufacturer Part") "0603WAF0000T5E")
        (field (name "Manufacturer") "UNI-ROYAL(厚声)")
      )
      (libsource (lib "easyedapro") (part "0603WAF0000T5E"))
    )
    (comp (ref "R24")
      (value "100kΩ")
      (footprint "easyedapro:R0603")
      (description "电阻类型:厚膜电阻;阻值:100kΩ;精度:±1%;功率:100mW;最大工作电压:75V;温度系数:±100ppm/°C;")
      (fields
        (field (name "Manufacturer Part") "0603WAF1003T5E")
        (field (name "Manufacturer") "UNI-ROYAL(厚声)")
      )
      (libsource (lib "easyedapro") (part "0603WAF1003T5E"))
    )
    (comp (ref "R25")
      (value "10kΩ")
      (description "电阻类型:厚膜电阻;阻值:10kΩ;精度:±1%;功率:100mW;最大工作电压:75V;温度系数:±100ppm/℃;")
      (fields
        (field (name "Manufacturer Part") "0603WAF1002T5E")
        (field (name "Manufacturer") "UNI-ROYAL(厚声)")
      )
      (libsource (lib "easyedapro") (part "电阻_1"))
    )
    (comp (ref "R26")
      (value "10kΩ")
      (footprint "easyedapro:R0603_1")
      (description "电阻类型:厚膜电阻;阻值:10kΩ;精度:±1%;功率:100mW;")
      (fields
        (field (name "Manufacturer Part") "0603WAF1002T5E")
        (field (name "Manufacturer") "UNI-ROYAL(厚声)")
      )
      (libsource (lib "easyedapro") (part "0603WAF1002T5E"))
    )
    (comp (ref "R27")
      (value "10kΩ")
      (footprint "easyedapro:R0603_1")
      (description "电阻类型:厚膜电阻;阻值:10kΩ;精度:±1%;功率:100mW;")
      (fields
        (field (name "Manufacturer Part") "0603WAF1002T5E")
        (field (name "Manufacturer") "UNI-ROYAL(厚声)")
      )
      (libsource (lib "easyedapro") (part "0603WAF1002T5E"))
    )
    (comp (ref "R28")
      (value "10kΩ")
      (footprint "easyedapro:R0603_1")
      (description "电阻类型:厚膜电阻;阻值:10kΩ;精度:±1%;功率:100mW;")
      (fields
        (field (name "Manufacturer Part") "0603WAF1002T5E")
        (field (name "Manufacturer") "UNI-ROYAL(厚声)")
      )
      (libsource (lib "easyedapro") (part "0603WAF1002T5E"))
    )
    (comp (ref "R29")
      (value "10kΩ")
      (footprint "easyedapro:R0603_1")
      (description "电阻类型:厚膜电阻;阻值:10kΩ;精度:±1%;功率:100mW;")
      (fields
        (field (name "Manufacturer Part") "0603WAF1002T5E")
        (field (name "Manufacturer") "UNI-ROYAL(厚声)")
      )
      (libsource (lib "easyedapro") (part "0603WAF1002T5E"))
    )
    (comp (ref "R30")
      (value "10kΩ")
      (footprint "easyedapro:R0603_1")
      (description "电阻类型:厚膜电阻;阻值:10kΩ;精度:±1%;功率:100mW;")
      (fields
        (field (name "Manufacturer Part") "0603WAF1002T5E")
        (field (name "Manufacturer") "UNI-ROYAL(厚声)")
      )
      (libsource (lib "easyedapro") (part "0603WAF1002T5E"))
    )
    (comp (ref "R31")
      (value "10kΩ")
      (footprint "easyedapro:R0603_1")
      (description "电阻类型:厚膜电阻;阻值:10kΩ;精度:±1%;功率:100mW;")
      (fields
        (field (name "Manufacturer Part") "0603WAF1002T5E")
        (field (name "Manufacturer") "UNI-ROYAL(厚声)")
      )
      (libsource (lib "easyedapro") (part "0603WAF1002T5E"))
    )
    (comp (ref "R32")
      (value "10kΩ")
      (footprint "easyedapro:R0603_1")
      (description "电阻类型:厚膜电阻;阻值:10kΩ;精度:±1%;功率:100mW;")
      (fields
        (field (name "Manufacturer Part") "0603WAF1002T5E")
        (field (name "Manufacturer") "UNI-ROYAL(厚声)")
      )
      (libsource (lib "easyedapro") (part "0603WAF1002T5E"))
    )
    (comp (ref "R33")
      (value "0Ω")
      (footprint "easyedapro:R0603_1")
      (description "电阻类型:厚膜电阻;阻值:0Ω;精度:±1%;功率:100mW;")
      (fields
        (field (name "Manufacturer Part") "0603WAF0000T5E")
        (field (name "Manufacturer") "UNI-ROYAL(厚声)")
      )
      (libsource (lib "easyedapro") (part "0603WAF0000T5E"))
    )
    (comp (ref "R34")
      (value "0Ω")
      (footprint "easyedapro:R0603_1")
      (description "电阻类型:厚膜电阻;阻值:0Ω;精度:±1%;功率:100mW;")
      (fields
        (field (name "Manufacturer Part") "0603WAF0000T5E")
        (field (name "Manufacturer") "UNI-ROYAL(厚声)")
      )
      (libsource (lib "easyedapro") (part "0603WAF0000T5E"))
    )
    (comp (ref "R35")
      (value "0Ω")
      (footprint "easyedapro:R0603_1")
      (description "电阻类型:厚膜电阻;阻值:0Ω;精度:±1%;功率:100mW;")
      (fields
        (field (name "Manufacturer Part") "0603WAF0000T5E")
        (field (name "Manufacturer") "UNI-ROYAL(厚声)")
      )
      (libsource (lib "easyedapro") (part "0603WAF0000T5E"))
    )
    (comp (ref "U8")
      (value "CH340C")
      (footprint "easyedapro:SOP-16_L10.0-W3.9-P1.27-LS6.0-BL")
      (description "类型:Transceiver;协议类别:USB 2.0;驱动器/接收器数:-;数据速率:2Mbps;")
      (fields (field (name "Manufacturer") "WCH(南京沁恒)"))
      (libsource (lib "easyedapro") (part "CH340C"))
    )
    (comp (ref "U9")
      (value "MSM261S4030H0R")
      (fields (field (name "Manufacturer") "MEMS(敏芯微)"))
      (libsource (lib "easyedapro") (part "MSM261S4030H0R"))
    )
    (comp (ref "U10")
      (value "MAX98357AETE+T")
      (footprint "easyedapro:TQFN-16_L3.0-W3.0-P0.50-BL-EP1.5")
      (description "功放类型:-;扬声器通道数:单声道;输出功率:3.2Wx2@4Ω;")
      (fields (field (name "Manufacturer") "ADI(亚德诺)/MAXIM(美信)"))
      (libsource (lib "easyedapro") (part "MAX98357AETE+T"))
    )
    (comp (ref "U11")
      (value "HCZZ0015-2")
      (footprint "easyedapro:CONN-SMD_HCZZ0015-2")
      (fields (field (name "Manufacturer") "HC(虹成电子)"))
      (libsource (lib "easyedapro") (part "HCZZ0015-2"))
    )
    (comp (ref "CN1")
      (value "HC-1.25-3PWT")
      (footprint "easyedapro:CONN-SMD_HC-1.25-3PWT")
      (fields (field (name "Manufacturer") "HCTL(华灿天禄)"))
      (libsource (lib "easyedapro") (part "HC-1.25-3PWT"))
    )
    (comp (ref "CN2")
      (value "HC-1.25-3PWT")
      (footprint "easyedapro:CONN-SMD_HC-1.25-3PWT")
      (fields (field (name "Manufacturer") "HCTL(华灿天禄)"))
      (libsource (lib "easyedapro") (part "HC-1.25-3PWT"))
    )
    (comp (ref "CN3")
      (value "HC-1.25-3PWT")
      (footprint "easyedapro:CONN-SMD_HC-1.25-3PWT")
      (fields (field (name "Manufacturer") "HCTL(华灿天禄)"))
      (libsource (lib "easyedapro") (part "HC-1.25-3PWT"))
    )
    (comp (ref "FPC1")
      (value "1.25-4PWB")
      (footprint "easyedapro:CONN-SMD_1.25-4PWB")
      (description "插针结构:1x4P;间距:1.25mm;安装方式:卧贴;参考系列:-;总PIN数:4P;排数:1;每排PIN数:4;行距:-;额定电流:-;工作温度范围:-40°C~+85°C;")
      (fields (field (name "Manufacturer") "DEALON(德艺隆)"))
      (libsource (lib "easyedapro") (part "1.25-4PWB"))
    )
    (comp (ref "HDR1")
      (value "PZ254-2-10-S")
      (footprint "easyedapro:HDR-SMD_20P-P2.54-V-M-R2-C10-S7.4")
      (fields (field (name "Manufacturer") "HCTL(华灿天禄)"))
      (libsource (lib "easyedapro") (part "PZ254-2-10-S"))
    )
    (comp (ref "M1")
      (value "~")
      (footprint "easyedapro:M3*5安装孔")
      (libsource (lib "easyedapro") (part "M3螺丝"))
    )
    (comp (ref "M2")
      (value "~")
      (footprint "easyedapro:M3*5安装孔")
      (libsource (lib "easyedapro") (part "M3螺丝"))
    )
    (comp (ref "M3")
      (value "~")
      (footprint "easyedapro:M3*5安装孔")
      (libsource (lib "easyedapro") (part "M3螺丝"))
    )
    (comp (ref "M4")
      (value "~")
      (footprint "easyedapro:M3*5安装孔")
      (libsource (lib "easyedapro") (part "M3螺丝"))
    )
    (comp (ref "R36")
      (value "0Ω")
      (footprint "easyedapro:R0603_1")
      (description "电阻类型:厚膜电阻;阻值:0Ω;精度:±1%;功率:100mW;")
      (fields
        (field (name "Manufacturer Part") "0603WAF0000T5E")
        (field (name "Manufacturer") "UNI-ROYAL(厚声)")
      )
      (libsource (lib "easyedapro") (part "0603WAF0000T5E"))
    )
    (comp (ref "R37")
      (value "0Ω")
      (footprint "easyedapro:R0603_1")
      (description "电阻类型:厚膜电阻;阻值:0Ω;精度:±1%;功率:100mW;")
      (fields
        (field (name "Manufacturer Part") "0603WAF0000T5E")
        (field (name "Manufacturer") "UNI-ROYAL(厚声)")
      )
      (libsource (lib "easyedapro") (part "0603WAF0000T5E"))
    )
    (comp (ref "R38")
      (value "0Ω")
      (footprint "easyedapro:R0603_1")
      (description "电阻类型:厚膜电阻;阻值:0Ω;精度:±1%;功率:100mW;")
      (fields
        (field (name "Manufacturer Part") "0603WAF0000T5E")
        (field (name "Manufacturer") "UNI-ROYAL(厚声)")
      )
      (libsource (lib "easyedapro") (part "0603WAF0000T5E"))
    )
    (comp (ref "R39")
      (value "0Ω")
      (footprint "easyedapro:R0603_1")
      (description "电阻类型:厚膜电阻;阻值:0Ω;精度:±1%;功率:100mW;")
      (fields
        (field (name "Manufacturer Part") "0603WAF0000T5E")
        (field (name "Manufacturer") "UNI-ROYAL(厚声)")
      )
      (libsource (lib "easyedapro") (part "0603WAF0000T5E"))
    )
    (comp (ref "R40")
      (value "0Ω")
      (footprint "easyedapro:R0603_1")
      (description "电阻类型:厚膜电阻;阻值:0Ω;精度:±1%;功率:100mW;")
      (fields
        (field (name "Manufacturer Part") "0603WAF0000T5E")
        (field (name "Manufacturer") "UNI-ROYAL(厚声)")
      )
      (libsource (lib "easyedapro") (part "0603WAF0000T5E"))
    )
  )
  (nets
    (net (code "1") (name "ASR_PB5") (class "Default")
      (node (ref "FPC1") (pin "4") (pinfunction "4_4") (pintype "unspecified"))
      (node (ref "R37") (pin "1") (pinfunction "1_1") (pintype "input"))
    )
    (net (code "2") (name "ASR_PB6") (class "Default")
      (node (ref "FPC1") (pin "3") (pinfunction "3_3") (pintype "unspecified"))
      (node (ref "R36") (pin "1") (pinfunction "1_1") (pintype "input"))
    )
    (net (code "3") (name "AUX_VCC") (class "Default")
      (node (ref "C1") (pin "2") (pinfunction "2_2") (pintype "input"))
      (node (ref "D1") (pin "1") (pinfunction "-_1") (pintype "unspecified"))
      (node (ref "Q1") (pin "2") (pinfunction "S_2") (pintype "unspecified"))
      (node (ref "SW1") (pin "4") (pinfunction "4_4") (pintype "unspecified"))
    )
    (net (code "4") (name "BAT_CHRG") (class "Default")
      (node (ref "LED2") (pin "1") (pinfunction "K_1") (pintype "input"))
      (node (ref "U4") (pin "7") (pinfunction "CHRG#_7") (pintype "input"))
    )
    (net (code "5") (name "BAT_STBY") (class "Default")
      (node (ref "U4") (pin "6") (pinfunction "STDBY#_6") (pintype "input"))
      (node (ref "U5") (pin "1") (pinfunction "K_1") (pintype "unspecified"))
    )
    (net (code "6") (name "DTR") (class "Default")
      (node (ref "Q4") (pin "2") (pinfunction "E_2") (pintype "unspecified"))
      (node (ref "R25") (pin "2") (pinfunction "2_2") (pintype "input"))
      (node (ref "U8") (pin "13") (pinfunction "DTR#_13") (pintype "input"))
    )
    (net (code "7") (name "EN_RST") (class "Default")
      (node (ref "C11") (pin "2") (pinfunction "2_2") (pintype "input"))
      (node (ref "Q5") (pin "3") (pinfunction "C_3") (pintype "unspecified"))
      (node (ref "R18") (pin "1") (pinfunction "1_1") (pintype "input"))
      (node (ref "SW3") (pin "3") (pinfunction "3_3") (pintype "input"))
      (node (ref "U7") (pin "3") (pinfunction "EN_3") (pintype "unspecified"))
    )
    (net (code "8") (name "GAIN_CTRL") (class "Default")
      (node (ref "R31") (pin "2") (pinfunction "2_2") (pintype "input"))
      (node (ref "R32") (pin "2") (pinfunction "2_2") (pintype "input"))
      (node (ref "U10") (pin "2") (pinfunction "GAIN_SLOT_2") (pintype "unspecified"))
    )
    (net (code "9") (name "GND") (class "Default")
      (node (ref "C1") (pin "1") (pinfunction "1_1") (pintype "input"))
      (node (ref "C10") (pin "1") (pinfunction "1_1") (pintype "input"))
      (node (ref "C11") (pin "1") (pinfunction "1_1") (pintype "input"))
      (node (ref "C12") (pin "2") (pinfunction "2_2") (pintype "input"))
      (node (ref "C13") (pin "2") (pinfunction "2_2") (pintype "input"))
      (node (ref "C14") (pin "2") (pinfunction "2_2") (pintype "input"))
      (node (ref "C15") (pin "2") (pinfunction "2_2") (pintype "input"))
      (node (ref "C16") (pin "1") (pinfunction "1_1") (pintype "input"))
      (node (ref "C17") (pin "1") (pinfunction "1_1") (pintype "input"))
      (node (ref "C2") (pin "1") (pinfunction "1_1") (pintype "input"))
      (node (ref "C3") (pin "1") (pinfunction "1_1") (pintype "input"))
      (node (ref "C5") (pin "2") (pinfunction "2_2") (pintype "input"))
      (node (ref "C6") (pin "2") (pinfunction "2_2") (pintype "input"))
      (node (ref "C7") (pin "1") (pinfunction "1_1") (pintype "input"))
      (node (ref "C8") (pin "1") (pinfunction "1_1") (pintype "input"))
      (node (ref "C9") (pin "1") (pinfunction "1_1") (pintype "input"))
      (node (ref "CN1") (pin "2") (pinfunction "2_2") (pintype "unspecified"))
      (node (ref "CN1") (pin "4") (pinfunction "4_4") (pintype "unspecified"))
      (node (ref "CN1") (pin "5") (pinfunction "5_5") (pintype "unspecified"))
      (node (ref "CN2") (pin "2") (pinfunction "2_2") (pintype "unspecified"))
      (node (ref "CN2") (pin "4") (pinfunction "4_4") (pintype "unspecified"))
      (node (ref "CN2") (pin "5") (pinfunction "5_5") (pintype "unspecified"))
      (node (ref "CN3") (pin "2") (pinfunction "2_2") (pintype "unspecified"))
      (node (ref "CN3") (pin "4") (pinfunction "4_4") (pintype "unspecified"))
      (node (ref "CN3") (pin "5") (pinfunction "5_5") (pintype "unspecified"))
      (node (ref "FPC1") (pin "2") (pinfunction "2_2") (pintype "unspecified"))
      (node (ref "FPC1") (pin "5") (pinfunction "5_5") (pintype "unspecified"))
      (node (ref "FPC1") (pin "6") (pinfunction "6_6") (pintype "unspecified"))
      (node (ref "HDR1") (pin "3") (pinfunction "3_3") (pintype "unspecified"))
      (node (ref "HDR1") (pin "4") (pinfunction "4_4") (pintype "unspecified"))
      (node (ref "LED1") (pin "1") (pinfunction "K_1") (pintype "input"))
      (node (ref "R1") (pin "1") (pinfunction "1_1") (pintype "input"))
      (node (ref "R11") (pin "1") (pinfunction "1_1") (pintype "input"))
      (node (ref "R14") (pin "1") (pinfunction "1_1") (pintype "input"))
      (node (ref "R16") (pin "1") (pinfunction "1_1") (pintype "input"))
      (node (ref "R2") (pin "2") (pinfunction "2_2") (pintype "input"))
      (node (ref "R24") (pin "1") (pinfunction "1_1") (pintype "input"))
      (node (ref "R28") (pin "2") (pinfunction "2_2") (pintype "input"))
      (node (ref "R29") (pin "1") (pinfunction "1_1") (pintype "input"))
      (node (ref "R31") (pin "1") (pinfunction "1_1") (pintype "input"))
      (node (ref "R4") (pin "1") (pinfunction "1_1") (pintype "input"))
      (node (ref "R5") (pin "1") (pinfunction "1_1") (pintype "input"))
      (node (ref "R6") (pin "2") (pinfunction "2_2") (pintype "input"))
      (node (ref "SW2") (pin "4") (pinfunction "4_4") (pintype "input"))
      (node (ref "SW3") (pin "4") (pinfunction "4_4") (pintype "input"))
      (node (ref "U1") (pin "17") (pinfunction "17_17") (pintype "input"))
      (node (ref "U1") (pin "18") (pinfunction "18_18") (pintype "input"))
      (node (ref "U1") (pin "19") (pinfunction "19_19") (pintype "input"))
      (node (ref "U1") (pin "20") (pinfunction "20_20") (pintype "input"))
      (node (ref "U1") (pin "A1") (pinfunction "GND_A1") (pintype "input"))
      (node (ref "U1") (pin "A12") (pinfunction "GND_A12") (pintype "input"))
      (node (ref "U1") (pin "B1") (pinfunction "GND_B1") (pintype "input"))
      (node (ref "U1") (pin "B12") (pinfunction "GND_B12") (pintype "input"))
      (node (ref "U10") (pin "11") (pinfunction "GND_11") (pintype "unspecified"))
      (node (ref "U10") (pin "15") (pinfunction "GND_15") (pintype "unspecified"))
      (node (ref "U10") (pin "17") (pinfunction "EP_17") (pintype "unspecified"))
      (node (ref "U10") (pin "3") (pinfunction "GND_3") (pintype "unspecified"))
      (node (ref "U11") (pin "3") (pinfunction "3_3") (pintype "unspecified"))
      (node (ref "U11") (pin "4") (pinfunction "4_4") (pintype "unspecified"))
      (node (ref "U2") (pin "17") (pinfunction "17_17") (pintype "input"))
      (node (ref "U2") (pin "18") (pinfunction "18_18") (pintype "input"))
      (node (ref "U2") (pin "19") (pinfunction "19_19") (pintype "input"))
      (node (ref "U2") (pin "20") (pinfunction "20_20") (pintype "input"))
      (node (ref "U2") (pin "A1") (pinfunction "GND_A1") (pintype "input"))
      (node (ref "U2") (pin "A12") (pinfunction "GND_A12") (pintype "input"))
      (node (ref "U2") (pin "B1") (pinfunction "GND_B1") (pintype "input"))
      (node (ref "U2") (pin "B12") (pinfunction "GND_B12") (pintype "input"))
      (node (ref "U3") (pin "2") (pinfunction "GND_2") (pintype "input"))
      (node (ref "U4") (pin "1") (pinfunction "TEMP_1") (pintype "input"))
      (node (ref "U4") (pin "3") (pinfunction "GND_3") (pintype "input"))
      (node (ref "U4") (pin "9") (pinfunction "EP_9") (pintype "input"))
      (node (ref "U6") (pin "2") (pinfunction "2_2") (pintype "unspecified"))
      (node (ref "U6") (pin "3") (pinfunction "3_3") (pintype "unspecified"))
      (node (ref "U6") (pin "4") (pinfunction "4_4") (pintype "unspecified"))
      (node (ref "U7") (pin "1") (pinfunction "GND_1") (pintype "unspecified"))
      (node (ref "U7") (pin "40") (pinfunction "GND_40") (pintype "unspecified"))
      (node (ref "U7") (pin "41") (pinfunction "GND_41") (pintype "unspecified"))
      (node (ref "U8") (pin "1") (pinfunction "GND_1") (pintype "input"))
      (node (ref "U9") (pin "1") (pinfunction "GND_1") (pintype "input"))
    )
    (net (code "10") (name "IO0_BOOT") (class "Default")
      (node (ref "Q4") (pin "3") (pinfunction "C_3") (pintype "unspecified"))
      (node (ref "SW2") (pin "3") (pinfunction "3_3") (pintype "input"))
      (node (ref "U7") (pin "27") (pinfunction "IO0_27") (pintype "unspecified"))
    )
    (net (code "11") (name "IO1_EXD") (class "Default")
      (node (ref "HDR1") (pin "6") (pinfunction "6_6") (pintype "unspecified"))
      (node (ref "U7") (pin "39") (pinfunction "IO1_39") (pintype "unspecified"))
    )
    (net (code "12") (name "IO2_EXD") (class "Default")
      (node (ref "HDR1") (pin "8") (pinfunction "8_8") (pintype "unspecified"))
      (node (ref "U7") (pin "38") (pinfunction "IO2_38") (pintype "unspecified"))
    )
    (net (code "13") (name "IO3_EXD") (class "Default")
      (node (ref "HDR1") (pin "5") (pinfunction "5_5") (pintype "unspecified"))
      (node (ref "U7") (pin "15") (pinfunction "IO3_15") (pintype "unspecified"))
    )
    (net (code "14") (name "IO4_SCK") (class "Default")
      (node (ref "U7") (pin "4") (pinfunction "IO4_4") (pintype "unspecified"))
      (node (ref "U9") (pin "6") (pinfunction "SCK_6") (pintype "input"))
    )
    (net (code "15") (name "IO5_WS") (class "Default")
      (node (ref "U7") (pin "5") (pinfunction "IO5_5") (pintype "unspecified"))
      (node (ref "U9") (pin "3") (pinfunction "WS_3") (pintype "input"))
    )
    (net (code "16") (name "IO6_SD") (class "Default")
      (node (ref "R24") (pin "2") (pinfunction "2_2") (pintype "input"))
      (node (ref "U7") (pin "6") (pinfunction "IO6_6") (pintype "unspecified"))
      (node (ref "U9") (pin "7") (pinfunction "SD_7") (pintype "input"))
    )
    (net (code "17") (name "IO7_KNOB") (class "Default")
      (node (ref "R38") (pin "2") (pinfunction "2_2") (pintype "input"))
      (node (ref "U7") (pin "7") (pinfunction "IO7_7") (pintype "unspecified"))
    )
    (net (code "18") (name "IO8_BAT_ADC") (class "Default")
      (node (ref "R15") (pin "1") (pinfunction "1_1") (pintype "input"))
      (node (ref "R16") (pin "2") (pinfunction "2_2") (pintype "input"))
      (node (ref "U7") (pin "12") (pinfunction "IO8_12") (pintype "unspecified"))
    )
    (net (code "19") (name "IO9_EXD") (class "Default")
      (node (ref "HDR1") (pin "9") (pinfunction "9_9") (pintype "unspecified"))
      (node (ref "U7") (pin "17") (pinfunction "IO9_17") (pintype "unspecified"))
    )
    (net (code "20") (name "IO10_BTN") (class "Default")
      (node (ref "R39") (pin "2") (pinfunction "2_2") (pintype "input"))
      (node (ref "U7") (pin "18") (pinfunction "IO10_18") (pintype "unspecified"))
    )
    (net (code "21") (name "IO11_TX_TW") (class "Default")
      (node (ref "R36") (pin "2") (pinfunction "2_2") (pintype "input"))
      (node (ref "U7") (pin "19") (pinfunction "IO11_19") (pintype "unspecified"))
    )
    (net (code "22") (name "IO12_RX_TW") (class "Default")
      (node (ref "R37") (pin "2") (pinfunction "2_2") (pintype "input"))
      (node (ref "U7") (pin "20") (pinfunction "IO12_20") (pintype "unspecified"))
    )
    (net (code "23") (name "IO13_EXD") (class "Default")
      (node (ref "HDR1") (pin "15") (pinfunction "15_15") (pintype "unspecified"))
      (node (ref "U7") (pin "21") (pinfunction "IO13_21") (pintype "unspecified"))
    )
    (net (code "24") (name "IO14_EXD") (class "Default")
      (node (ref "HDR1") (pin "13") (pinfunction "13_13") (pintype "unspecified"))
      (node (ref "U7") (pin "22") (pinfunction "IO14_22") (pintype "unspecified"))
    )
    (net (code "25") (name "IO15_DIN") (class "Default")
      (node (ref "U10") (pin "1") (pinfunction "DIN_1") (pintype "unspecified"))
      (node (ref "U7") (pin "8") (pinfunction "IO15_8") (pintype "unspecified"))
    )
    (net (code "26") (name "IO16_BCLK") (class "Default")
      (node (ref "U10") (pin "16") (pinfunction "BCLK_16") (pintype "unspecified"))
      (node (ref "U7") (pin "9") (pinfunction "IO16_9") (pintype "unspecified"))
    )
    (net (code "27") (name "IO17_LR") (class "Default")
      (node (ref "U10") (pin "14") (pinfunction "LRCLK_14") (pintype "unspecified"))
      (node (ref "U7") (pin "10") (pinfunction "IO17_10") (pintype "unspecified"))
    )
    (net (code "28") (name "IO18_LED") (class "Default")
      (node (ref "R40") (pin "2") (pinfunction "2_2") (pintype "input"))
      (node (ref "U7") (pin "11") (pinfunction "IO18_11") (pintype "unspecified"))
    )
    (net (code "29") (name "IO19_USB_D-") (class "Default")
      (node (ref "R19") (pin "2") (pinfunction "2_2") (pintype "input"))
      (node (ref "U1") (pin "A7") (pinfunction "DN1_A7") (pintype "input"))
      (node (ref "U1") (pin "B7") (pinfunction "DN2_B7") (pintype "input"))
    )
    (net (code "30") (name "IO20_USB_D+") (class "Default")
      (node (ref "R20") (pin "2") (pinfunction "2_2") (pintype "input"))
      (node (ref "U1") (pin "A6") (pinfunction "DP1_A6") (pintype "input"))
      (node (ref "U1") (pin "B6") (pinfunction "DP2_B6") (pintype "input"))
    )
    (net (code "31") (name "IO21_EXD") (class "Default")
      (node (ref "HDR1") (pin "11") (pinfunction "11_11") (pintype "unspecified"))
      (node (ref "U7") (pin "23") (pinfunction "IO21_23") (pintype "unspecified"))
    )
    (net (code "32") (name "IO38_EXD") (class "Default")
      (node (ref "HDR1") (pin "18") (pinfunction "18_18") (pintype "unspecified"))
      (node (ref "U7") (pin "31") (pinfunction "IO38_31") (pintype "unspecified"))
    )
    (net (code "33") (name "IO39_EXD") (class "Default")
      (node (ref "HDR1") (pin "16") (pinfunction "16_16") (pintype "unspecified"))
      (node (ref "U7") (pin "32") (pinfunction "IO39_32") (pintype "unspecified"))
    )
    (net (code "34") (name "IO40_EXD") (class "Default")
      (node (ref "HDR1") (pin "14") (pinfunction "14_14") (pintype "unspecified"))
      (node (ref "U7") (pin "33") (pinfunction "IO40_33") (pintype "unspecified"))
    )
    (net (code "35") (name "IO41_EXD") (class "Default")
      (node (ref "HDR1") (pin "12") (pinfunction "12_12") (pintype "unspecified"))
      (node (ref "U7") (pin "34") (pinfunction "IO41_34") (pintype "unspecified"))
    )
    (net (code "36") (name "IO42_EXD") (class "Default")
      (node (ref "HDR1") (pin "10") (pinfunction "10_10") (pintype "unspecified"))
      (node (ref "U7") (pin "35") (pinfunction "IO42_35") (pintype "unspecified"))
    )
    (net (code "37") (name "IO43_TX") (class "Default")
      (node (ref "R23") (pin "2") (pinfunction "2_2") (pintype "input"))
      (node (ref "U7") (pin "37") (pinfunction "TXD0_37") (pintype "unspecified"))
    )
    (net (code "38") (name "IO44_RX") (class "Default")
      (node (ref "R22") (pin "2") (pinfunction "2_2") (pintype "input"))
      (node (ref "U7") (pin "36") (pinfunction "RXD0_36") (pintype "unspecified"))
    )
    (net (code "39") (name "IO45_EXD") (class "Default")
      (node (ref "HDR1") (pin "20") (pinfunction "20_20") (pintype "unspecified"))
      (node (ref "U7") (pin "26") (pinfunction "IO45_26") (pintype "unspecified"))
    )
    (net (code "40") (name "IO46_EXD") (class "Default")
      (node (ref "HDR1") (pin "7") (pinfunction "7_7") (pintype "unspecified"))
      (node (ref "U7") (pin "16") (pinfunction "IO46_16") (pintype "unspecified"))
    )
    (net (code "41") (name "IO47_EXD") (class "Default")
      (node (ref "HDR1") (pin "17") (pinfunction "17_17") (pintype "unspecified"))
      (node (ref "U7") (pin "24") (pinfunction "IO47_24") (pintype "unspecified"))
    )
    (net (code "42") (name "IO48_EXD") (class "Default")
      (node (ref "HDR1") (pin "19") (pinfunction "19_19") (pintype "unspecified"))
      (node (ref "U7") (pin "25") (pinfunction "IO48_25") (pintype "unspecified"))
    )
    (net (code "43") (name "MAX_3V3") (class "Default")
      (node (ref "C14") (pin "1") (pinfunction "1_1") (pintype "input"))
      (node (ref "C15") (pin "1") (pinfunction "1_1") (pintype "input"))
      (node (ref "R30") (pin "1") (pinfunction "1_1") (pintype "input"))
      (node (ref "R32") (pin "1") (pinfunction "1_1") (pintype "input"))
      (node (ref "R33") (pin "2") (pinfunction "2_2") (pintype "input"))
      (node (ref "U10") (pin "7") (pinfunction "VDD_7") (pintype "unspecified"))
      (node (ref "U10") (pin "8") (pinfunction "VDD_8") (pintype "unspecified"))
    )
    (net (code "44") (name "Net-(C4-Pad2)") (class "Default")
      (node (ref "C4") (pin "2") (pinfunction "2_2") (pintype "input"))
      (node (ref "C5") (pin "1") (pinfunction "1_1") (pintype "input"))
      (node (ref "C6") (pin "1") (pinfunction "1_1") (pintype "input"))
      (node (ref "L1") (pin "2") (pinfunction "2_2") (pintype "input"))
      (node (ref "R7") (pin "1") (pinfunction "1_1") (pintype "input"))
      (node (ref "R9") (pin "2") (pinfunction "2_2") (pintype "input"))
    )
    (net (code "45") (name "Net-(C16-Pad2)") (class "Default")
      (node (ref "C16") (pin "2") (pinfunction "2_2") (pintype "input"))
      (node (ref "R35") (pin "2") (pinfunction "2_2") (pintype "input"))
      (node (ref "U11") (pin "1") (pinfunction "1_1") (pintype "unspecified"))
    )
    (net (code "46") (name "Net-(C17-Pad2)") (class "Default")
      (node (ref "C17") (pin "2") (pinfunction "2_2") (pintype "input"))
      (node (ref "R34") (pin "2") (pinfunction "2_2") (pintype "input"))
      (node (ref "U11") (pin "2") (pinfunction "2_2") (pintype "unspecified"))
    )
    (net (code "47") (name "Net-(CN1-Pad3)") (class "Default")
      (node (ref "CN1") (pin "3") (pinfunction "3_3") (pintype "unspecified"))
      (node (ref "R38") (pin "1") (pinfunction "1_1") (pintype "input"))
    )
    (net (code "48") (name "Net-(CN2-Pad3)") (class "Default")
      (node (ref "CN2") (pin "3") (pinfunction "3_3") (pintype "unspecified"))
      (node (ref "R39") (pin "1") (pinfunction "1_1") (pintype "input"))
    )
    (net (code "49") (name "Net-(CN3-Pad3)") (class "Default")
      (node (ref "CN3") (pin "3") (pinfunction "3_3") (pintype "unspecified"))
      (node (ref "R40") (pin "1") (pinfunction "1_1") (pintype "input"))
    )
    (net (code "50") (name "Net-(LED1-A)") (class "Default")
      (node (ref "LED1") (pin "2") (pinfunction "A_2") (pintype "input"))
      (node (ref "R10") (pin "2") (pinfunction "2_2") (pintype "input"))
    )
    (net (code "51") (name "Net-(LED2-A)") (class "Default")
      (node (ref "LED2") (pin "2") (pinfunction "A_2") (pintype "input"))
      (node (ref "R13") (pin "2") (pinfunction "2_2") (pintype "input"))
    )
    (net (code "52") (name "Net-(Q1-G)") (class "Default")
      (node (ref "Q1") (pin "1") (pinfunction "G_1") (pintype "unspecified"))
      (node (ref "R3") (pin "1") (pinfunction "1_1") (pintype "input"))
    )
    (net (code "53") (name "Net-(Q4-B)") (class "Default")
      (node (ref "Q4") (pin "1") (pinfunction "B_1") (pintype "unspecified"))
      (node (ref "R21") (pin "1") (pinfunction "1_1") (pintype "input"))
    )
    (net (code "54") (name "Net-(Q5-B)") (class "Default")
      (node (ref "Q5") (pin "1") (pinfunction "B_1") (pintype "unspecified"))
      (node (ref "R25") (pin "1") (pinfunction "1_1") (pintype "input"))
    )
    (net (code "55") (name "Net-(U1-CC1)") (class "Default")
      (node (ref "R1") (pin "2") (pinfunction "2_2") (pintype "input"))
      (node (ref "U1") (pin "A5") (pinfunction "CC1_A5") (pintype "input"))
    )
    (net (code "56") (name "Net-(U1-CC2)") (class "Default")
      (node (ref "R2") (pin "1") (pinfunction "1_1") (pintype "input"))
      (node (ref "U1") (pin "B5") (pinfunction "CC2_B5") (pintype "input"))
    )
    (net (code "57") (name "Net-(U2-CC1)") (class "Default")
      (node (ref "R5") (pin "2") (pinfunction "2_2") (pintype "input"))
      (node (ref "U2") (pin "A5") (pinfunction "CC1_A5") (pintype "input"))
    )
    (net (code "58") (name "Net-(U2-CC2)") (class "Default")
      (node (ref "R6") (pin "1") (pinfunction "1_1") (pintype "input"))
      (node (ref "U2") (pin "B5") (pinfunction "CC2_B5") (pintype "input"))
    )
    (net (code "59") (name "Net-(U3-EN)") (class "Default")
      (node (ref "R8") (pin "2") (pinfunction "2_2") (pintype "input"))
      (node (ref "U3") (pin "1") (pinfunction "EN_1") (pintype "input"))
    )
    (net (code "60") (name "Net-(U3-FB)") (class "Default")
      (node (ref "C4") (pin "1") (pinfunction "1_1") (pintype "input"))
      (node (ref "R11") (pin "2") (pinfunction "2_2") (pintype "input"))
      (node (ref "R9") (pin "1") (pinfunction "1_1") (pintype "input"))
      (node (ref "U3") (pin "5") (pinfunction "FB_5") (pintype "input"))
    )
    (net (code "61") (name "Net-(U3-IN)") (class "Default")
      (node (ref "C2") (pin "2") (pinfunction "2_2") (pintype "input"))
      (node (ref "C3") (pin "2") (pinfunction "2_2") (pintype "input"))
      (node (ref "F1") (pin "1") (pinfunction "1_1") (pintype "unspecified"))
      (node (ref "R8") (pin "1") (pinfunction "1_1") (pintype "input"))
      (node (ref "U3") (pin "4") (pinfunction "IN_4") (pintype "input"))
    )
    (net (code "62") (name "Net-(U3-SW)") (class "Default")
      (node (ref "L1") (pin "1") (pinfunction "1_1") (pintype "input"))
      (node (ref "U3") (pin "3") (pinfunction "SW_3") (pintype "input"))
    )
    (net (code "63") (name "Net-(U4-PROG)") (class "Default")
      (node (ref "R14") (pin "2") (pinfunction "2_2") (pintype "input"))
      (node (ref "U4") (pin "2") (pinfunction "PROG_2") (pintype "input"))
    )
    (net (code "64") (name "Net-(U5-A)") (class "Default")
      (node (ref "R12") (pin "2") (pinfunction "2_2") (pintype "input"))
      (node (ref "U5") (pin "2") (pinfunction "A_2") (pintype "unspecified"))
    )
    (net (code "65") (name "Net-(U7-3V3)") (class "Default")
      (node (ref "C10") (pin "2") (pinfunction "2_2") (pintype "input"))
      (node (ref "C9") (pin "2") (pinfunction "2_2") (pintype "input"))
      (node (ref "R17") (pin "2") (pinfunction "2_2") (pintype "input"))
      (node (ref "R18") (pin "2") (pinfunction "2_2") (pintype "input"))
      (node (ref "U7") (pin "2") (pinfunction "3V3_2") (pintype "unspecified"))
    )
    (net (code "66") (name "Net-(U7-IO19)") (class "Default")
      (node (ref "R19") (pin "1") (pinfunction "1_1") (pintype "input"))
      (node (ref "U7") (pin "13") (pinfunction "IO19_13") (pintype "unspecified"))
    )
    (net (code "67") (name "Net-(U7-IO20)") (class "Default")
      (node (ref "R20") (pin "1") (pinfunction "1_1") (pintype "input"))
      (node (ref "U7") (pin "14") (pinfunction "IO20_14") (pintype "unspecified"))
    )
    (net (code "68") (name "Net-(U8-RXD)") (class "Default")
      (node (ref "R23") (pin "1") (pinfunction "1_1") (pintype "input"))
      (node (ref "U8") (pin "3") (pinfunction "RXD_3") (pintype "input"))
    )
    (net (code "69") (name "Net-(U8-TXD)") (class "Default")
      (node (ref "R22") (pin "1") (pinfunction "1_1") (pintype "input"))
      (node (ref "U8") (pin "2") (pinfunction "TXD_2") (pintype "input"))
    )
    (net (code "70") (name "Net-(U9-CHIPEN)") (class "Default")
      (node (ref "R26") (pin "1") (pinfunction "1_1") (pintype "input"))
      (node (ref "U9") (pin "4") (pinfunction "CHIPEN_4") (pintype "input"))
    )
    (net (code "71") (name "Net-(U9-L{slash}R)") (class "Default")
      (node (ref "R27") (pin "1") (pinfunction "1_1") (pintype "input"))
      (node (ref "R28") (pin "1") (pinfunction "1_1") (pintype "input"))
      (node (ref "U9") (pin "5") (pinfunction "L/R_5") (pintype "input"))
    )
    (net (code "72") (name "Net-(U10-OUTN)") (class "Default")
      (node (ref "R34") (pin "1") (pinfunction "1_1") (pintype "input"))
      (node (ref "U10") (pin "10") (pinfunction "OUTN_10") (pintype "unspecified"))
    )
    (net (code "73") (name "Net-(U10-OUTP)") (class "Default")
      (node (ref "R35") (pin "1") (pinfunction "1_1") (pintype "input"))
      (node (ref "U10") (pin "9") (pinfunction "OUTP_9") (pintype "unspecified"))
    )
    (net (code "74") (name "RTS") (class "Default")
      (node (ref "Q5") (pin "2") (pinfunction "E_2") (pintype "unspecified"))
      (node (ref "R21") (pin "2") (pinfunction "2_2") (pintype "input"))
      (node (ref "U8") (pin "14") (pinfunction "RTS#_14") (pintype "input"))
    )
    (net (code "75") (name "SD_MODE") (class "Default")
      (node (ref "R29") (pin "2") (pinfunction "2_2") (pintype "input"))
      (node (ref "R30") (pin "2") (pinfunction "2_2") (pintype "input"))
      (node (ref "U10") (pin "4") (pinfunction "SD_MODE#_4") (pintype "unspecified"))
    )
    (net (code "76") (name "USB_5V") (class "Default")
      (node (ref "C7") (pin "2") (pinfunction "2_2") (pintype "input"))
      (node (ref "D1") (pin "2") (pinfunction "+_2") (pintype "unspecified"))
      (node (ref "HDR1") (pin "1") (pinfunction "1_1") (pintype "unspecified"))
      (node (ref "R12") (pin "1") (pinfunction "1_1") (pintype "input"))
      (node (ref "R13") (pin "1") (pinfunction "1_1") (pintype "input"))
      (node (ref "R3") (pin "2") (pinfunction "2_2") (pintype "input"))
      (node (ref "R4") (pin "2") (pinfunction "2_2") (pintype "input"))
      (node (ref "U1") (pin "A4") (pinfunction "VBUS_A4") (pintype "input"))
      (node (ref "U1") (pin "A9") (pinfunction "VBUS_A9") (pintype "input"))
      (node (ref "U1") (pin "B4") (pinfunction "VBUS_B4") (pintype "input"))
      (node (ref "U1") (pin "B9") (pinfunction "VBUS_B9") (pintype "input"))
      (node (ref "U2") (pin "A4") (pinfunction "VBUS_A4") (pintype "input"))
      (node (ref "U2") (pin "A9") (pinfunction "VBUS_A9") (pintype "input"))
      (node (ref "U2") (pin "B4") (pinfunction "VBUS_B4") (pintype "input"))
      (node (ref "U2") (pin "B9") (pinfunction "VBUS_B9") (pintype "input"))
      (node (ref "U4") (pin "4") (pinfunction "VCC_4") (pintype "input"))
      (node (ref "U4") (pin "8") (pinfunction "CE_8") (pintype "input"))
    )
    (net (code "77") (name "USB_D+") (class "Default")
      (node (ref "U2") (pin "A6") (pinfunction "DP1_A6") (pintype "input"))
      (node (ref "U2") (pin "B6") (pinfunction "DP2_B6") (pintype "input"))
      (node (ref "U8") (pin "5") (pinfunction "D+_5") (pintype "input"))
    )
    (net (code "78") (name "USB_D-") (class "Default")
      (node (ref "U2") (pin "A7") (pinfunction "DN1_A7") (pintype "input"))
      (node (ref "U2") (pin "B7") (pinfunction "DN2_B7") (pintype "input"))
      (node (ref "U8") (pin "6") (pinfunction "D-_6") (pintype "input"))
    )
    (net (code "79") (name "VBAT") (class "Default")
      (node (ref "C8") (pin "2") (pinfunction "2_2") (pintype "input"))
      (node (ref "Q1") (pin "3") (pinfunction "D_3") (pintype "unspecified"))
      (node (ref "R15") (pin "2") (pinfunction "2_2") (pintype "input"))
      (node (ref "U4") (pin "5") (pinfunction "BAT_5") (pintype "input"))
      (node (ref "U6") (pin "1") (pinfunction "1_1") (pintype "unspecified"))
    )
    (net (code "80") (name "VCC_3V3") (class "Default")
      (node (ref "C12") (pin "1") (pinfunction "1_1") (pintype "input"))
      (node (ref "C13") (pin "1") (pinfunction "1_1") (pintype "input"))
      (node (ref "CN1") (pin "1") (pinfunction "1_1") (pintype "unspecified"))
      (node (ref "CN2") (pin "1") (pinfunction "1_1") (pintype "unspecified"))
      (node (ref "CN3") (pin "1") (pinfunction "1_1") (pintype "unspecified"))
      (node (ref "FPC1") (pin "1") (pinfunction "1_1") (pintype "unspecified"))
      (node (ref "HDR1") (pin "2") (pinfunction "2_2") (pintype "unspecified"))
      (node (ref "R10") (pin "1") (pinfunction "1_1") (pintype "input"))
      (node (ref "R17") (pin "1") (pinfunction "1_1") (pintype "input"))
      (node (ref "R26") (pin "2") (pinfunction "2_2") (pintype "input"))
      (node (ref "R27") (pin "2") (pinfunction "2_2") (pintype "input"))
      (node (ref "R33") (pin "1") (pinfunction "1_1") (pintype "input"))
      (node (ref "R7") (pin "2") (pinfunction "2_2") (pintype "input"))
      (node (ref "U8") (pin "16") (pinfunction "VCC_16") (pintype "input"))
      (node (ref "U8") (pin "4") (pinfunction "V3_4") (pintype "input"))
      (node (ref "U9") (pin "8") (pinfunction "VDD_8") (pintype "input"))
    )
    (net (code "81") (name "VCC_BOARD") (class "Default")
      (node (ref "F1") (pin "2") (pinfunction "2_2") (pintype "unspecified"))
      (node (ref "SW1") (pin "5") (pinfunction "5_5") (pintype "unspecified"))
    )
    (net (code "82") (name "unconnected-(M1-Pad1)") (class "Default")
      (node (ref "M1") (pin "1") (pinfunction "1_1") (pintype "input+no_connect"))
    )
    (net (code "83") (name "unconnected-(M2-Pad1)") (class "Default")
      (node (ref "M2") (pin "1") (pinfunction "1_1") (pintype "input+no_connect"))
    )
    (net (code "84") (name "unconnected-(M3-Pad1)") (class "Default")
      (node (ref "M3") (pin "1") (pinfunction "1_1") (pintype "input+no_connect"))
    )
    (net (code "85") (name "unconnected-(M4-Pad1)") (class "Default")
      (node (ref "M4") (pin "1") (pinfunction "1_1") (pintype "input+no_connect"))
    )
    (net (code "86") (name "unconnected-(SW1-Pad1)") (class "Default")
      (node (ref "SW1") (pin "1") (pinfunction "1_1") (pintype "unspecified+no_connect"))
    )
    (net (code "87") (name "unconnected-(SW1-Pad2)") (class "Default")
      (node (ref "SW1") (pin "2") (pinfunction "2_2") (pintype "unspecified+no_connect"))
    )
    (net (code "88") (name "unconnected-(SW1-Pad3)") (class "Default")
      (node (ref "SW1") (pin "3") (pinfunction "3_3") (pintype "unspecified+no_connect"))
    )
    (net (code "89") (name "unconnected-(SW1-Pad6)") (class "Default")
      (node (ref "SW1") (pin "6") (pinfunction "6_6") (pintype "unspecified+no_connect"))
    )
    (net (code "90") (name "unconnected-(SW2-Pad1)") (class "Default")
      (node (ref "SW2") (pin "1") (pinfunction "1_1") (pintype "input+no_connect"))
    )
    (net (code "91") (name "unconnected-(SW2-Pad2)") (class "Default")
      (node (ref "SW2") (pin "2") (pinfunction "2_2") (pintype "input+no_connect"))
    )
    (net (code "92") (name "unconnected-(SW3-Pad1)") (class "Default")
      (node (ref "SW3") (pin "1") (pinfunction "1_1") (pintype "input+no_connect"))
    )
    (net (code "93") (name "unconnected-(SW3-Pad2)") (class "Default")
      (node (ref "SW3") (pin "2") (pinfunction "2_2") (pintype "input+no_connect"))
    )
    (net (code "94") (name "unconnected-(U1-SBU1-PadA8)") (class "Default")
      (node (ref "U1") (pin "A8") (pinfunction "SBU1_A8") (pintype "input+no_connect"))
    )
    (net (code "95") (name "unconnected-(U1-SBU2-PadB8)") (class "Default")
      (node (ref "U1") (pin "B8") (pinfunction "SBU2_B8") (pintype "input+no_connect"))
    )
    (net (code "96") (name "unconnected-(U2-SBU1-PadA8)") (class "Default")
      (node (ref "U2") (pin "A8") (pinfunction "SBU1_A8") (pintype "input+no_connect"))
    )
    (net (code "97") (name "unconnected-(U2-SBU2-PadB8)") (class "Default")
      (node (ref "U2") (pin "B8") (pinfunction "SBU2_B8") (pintype "input+no_connect"))
    )
    (net (code "98") (name "unconnected-(U7-IO35-Pad28)") (class "Default")
      (node (ref "U7") (pin "28") (pinfunction "IO35_28") (pintype "unspecified+no_connect"))
    )
    (net (code "99") (name "unconnected-(U7-IO36-Pad29)") (class "Default")
      (node (ref "U7") (pin "29") (pinfunction "IO36_29") (pintype "unspecified+no_connect"))
    )
    (net (code "100") (name "unconnected-(U7-IO37-Pad30)") (class "Default")
      (node (ref "U7") (pin "30") (pinfunction "IO37_30") (pintype "unspecified+no_connect"))
    )
    (net (code "101") (name "unconnected-(U8-CTS#-Pad9)") (class "Default")
      (node (ref "U8") (pin "9") (pinfunction "CTS#_9") (pintype "input+no_connect"))
    )
    (net (code "102") (name "unconnected-(U8-DCD#-Pad12)") (class "Default")
      (node (ref "U8") (pin "12") (pinfunction "DCD#_12") (pintype "input+no_connect"))
    )
    (net (code "103") (name "unconnected-(U8-DSR#-Pad10)") (class "Default")
      (node (ref "U8") (pin "10") (pinfunction "DSR#_10") (pintype "input+no_connect"))
    )
    (net (code "104") (name "unconnected-(U8-NC.-Pad7)") (class "Default")
      (node (ref "U8") (pin "7") (pinfunction "NC._7") (pintype "input+no_connect"))
    )
    (net (code "105") (name "unconnected-(U8-NC.-Pad8)") (class "Default")
      (node (ref "U8") (pin "8") (pinfunction "NC._8") (pintype "input+no_connect"))
    )
    (net (code "106") (name "unconnected-(U8-R232-Pad15)") (class "Default")
      (node (ref "U8") (pin "15") (pinfunction "R232_15") (pintype "input+no_connect"))
    )
    (net (code "107") (name "unconnected-(U8-RI#-Pad11)") (class "Default")
      (node (ref "U8") (pin "11") (pinfunction "RI#_11") (pintype "input+no_connect"))
    )
    (net (code "108") (name "unconnected-(U9-N{slash}C-Pad2)") (class "Default")
      (node (ref "U9") (pin "2") (pinfunction "N/C_2") (pintype "input+no_connect"))
    )
    (net (code "109") (name "unconnected-(U10-N.C.-Pad5)") (class "Default")
      (node (ref "U10") (pin "5") (pinfunction "N.C._5") (pintype "unspecified+no_connect"))
    )
    (net (code "110") (name "unconnected-(U10-N.C.-Pad6)") (class "Default")
      (node (ref "U10") (pin "6") (pinfunction "N.C._6") (pintype "unspecified+no_connect"))
    )
    (net (code "111") (name "unconnected-(U10-N.C.-Pad12)") (class "Default")
      (node (ref "U10") (pin "12") (pinfunction "N.C._12") (pintype "unspecified+no_connect"))
    )
    (net (code "112") (name "unconnected-(U10-N.C.-Pad13)") (class "Default")
      (node (ref "U10") (pin "13") (pinfunction "N.C._13") (pintype "unspecified+no_connect"))
    )
  )
)
